# pi3_hat.net
KiCad netlist of a schematic drawn in EAGLE
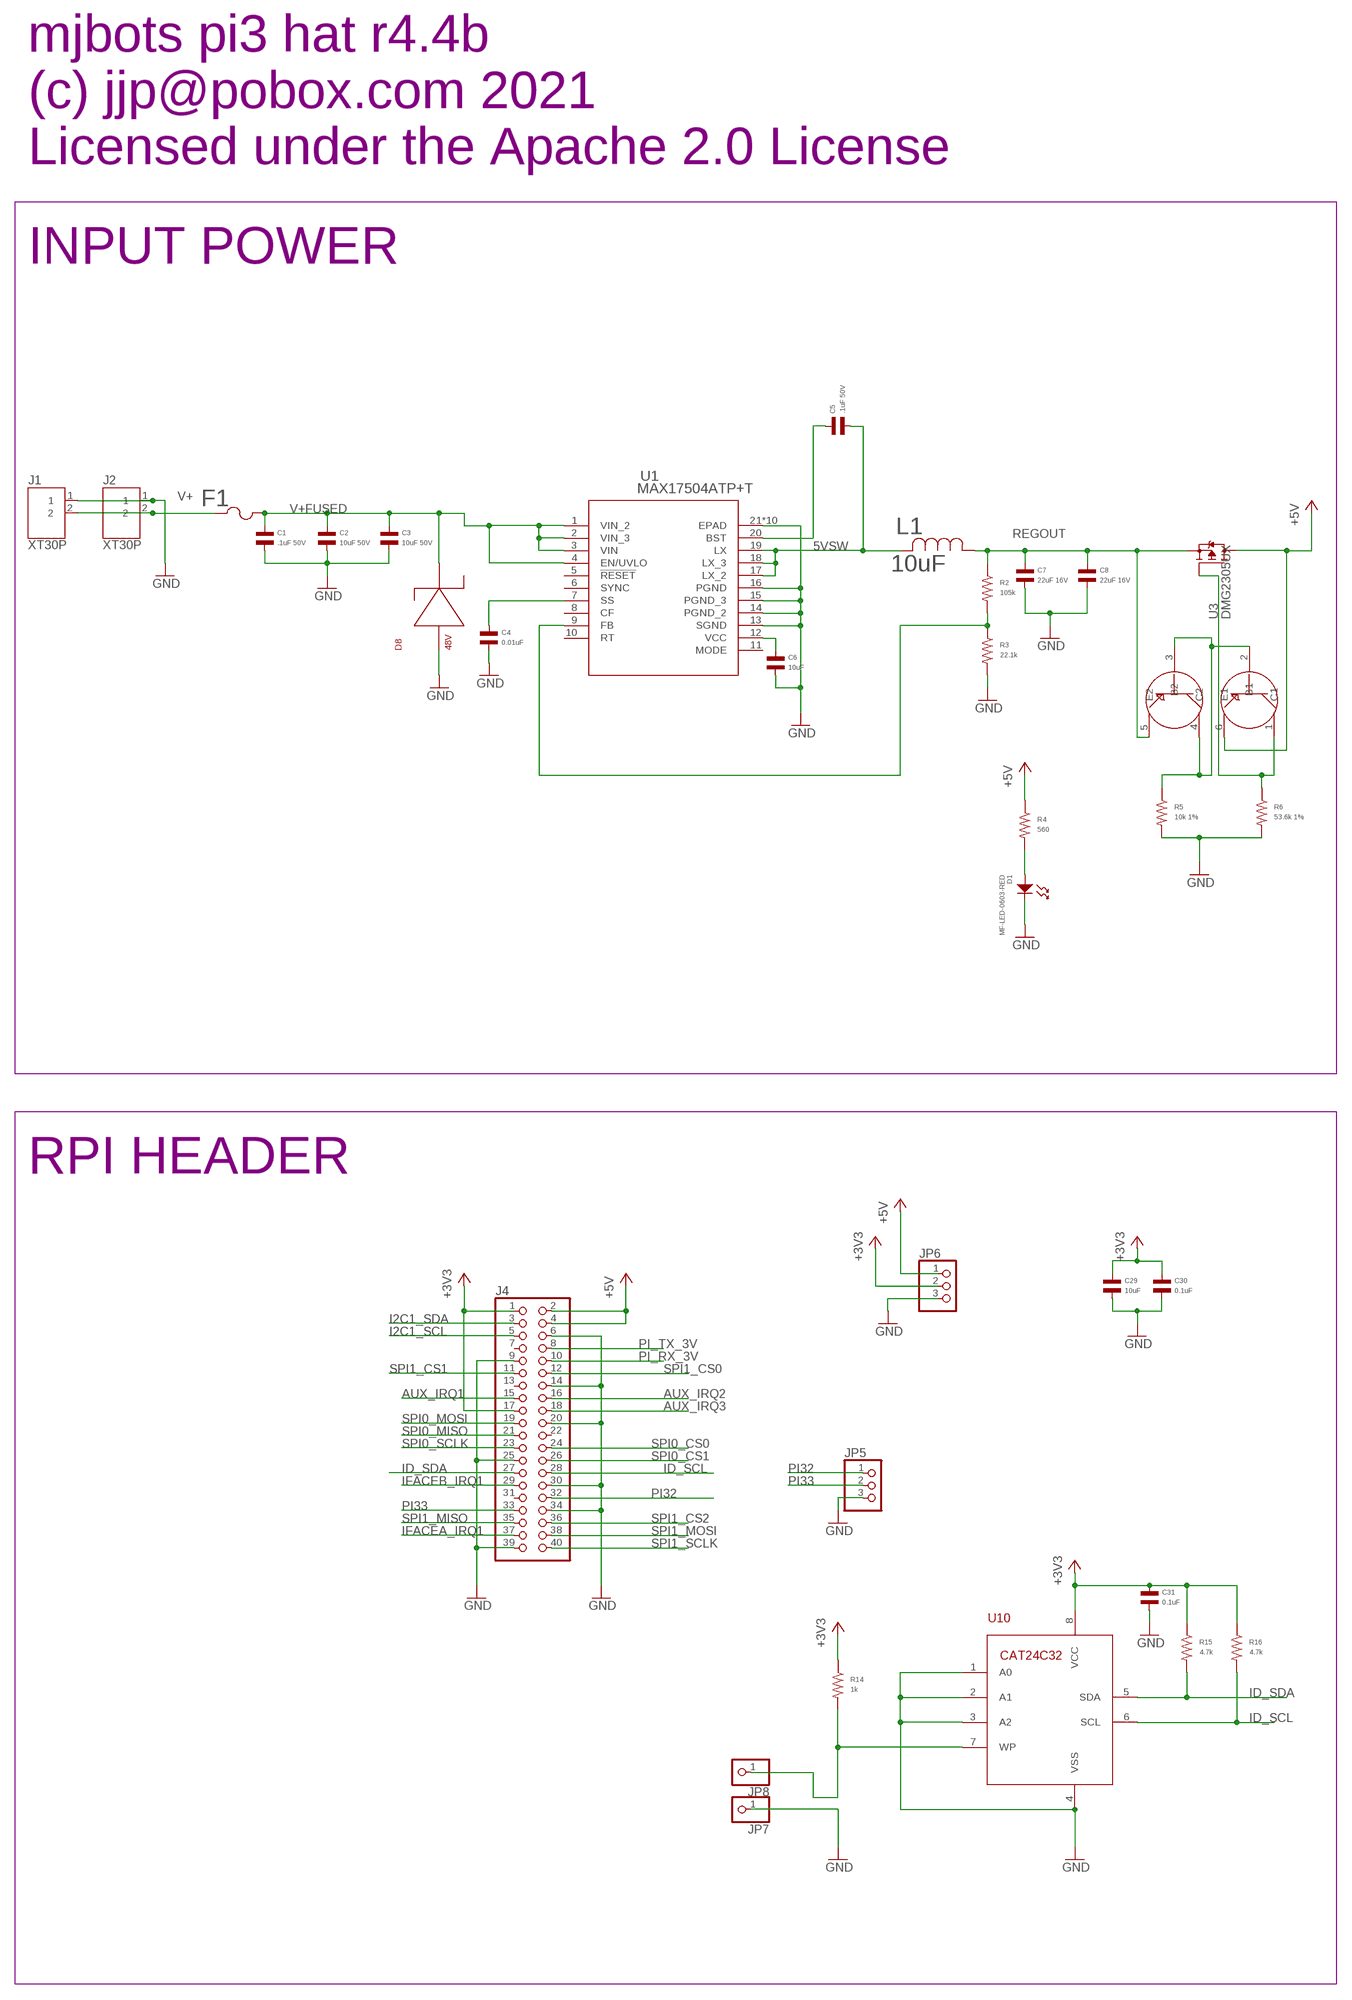
[diagram p0: schematic, sheet 1, part 1 of 3]
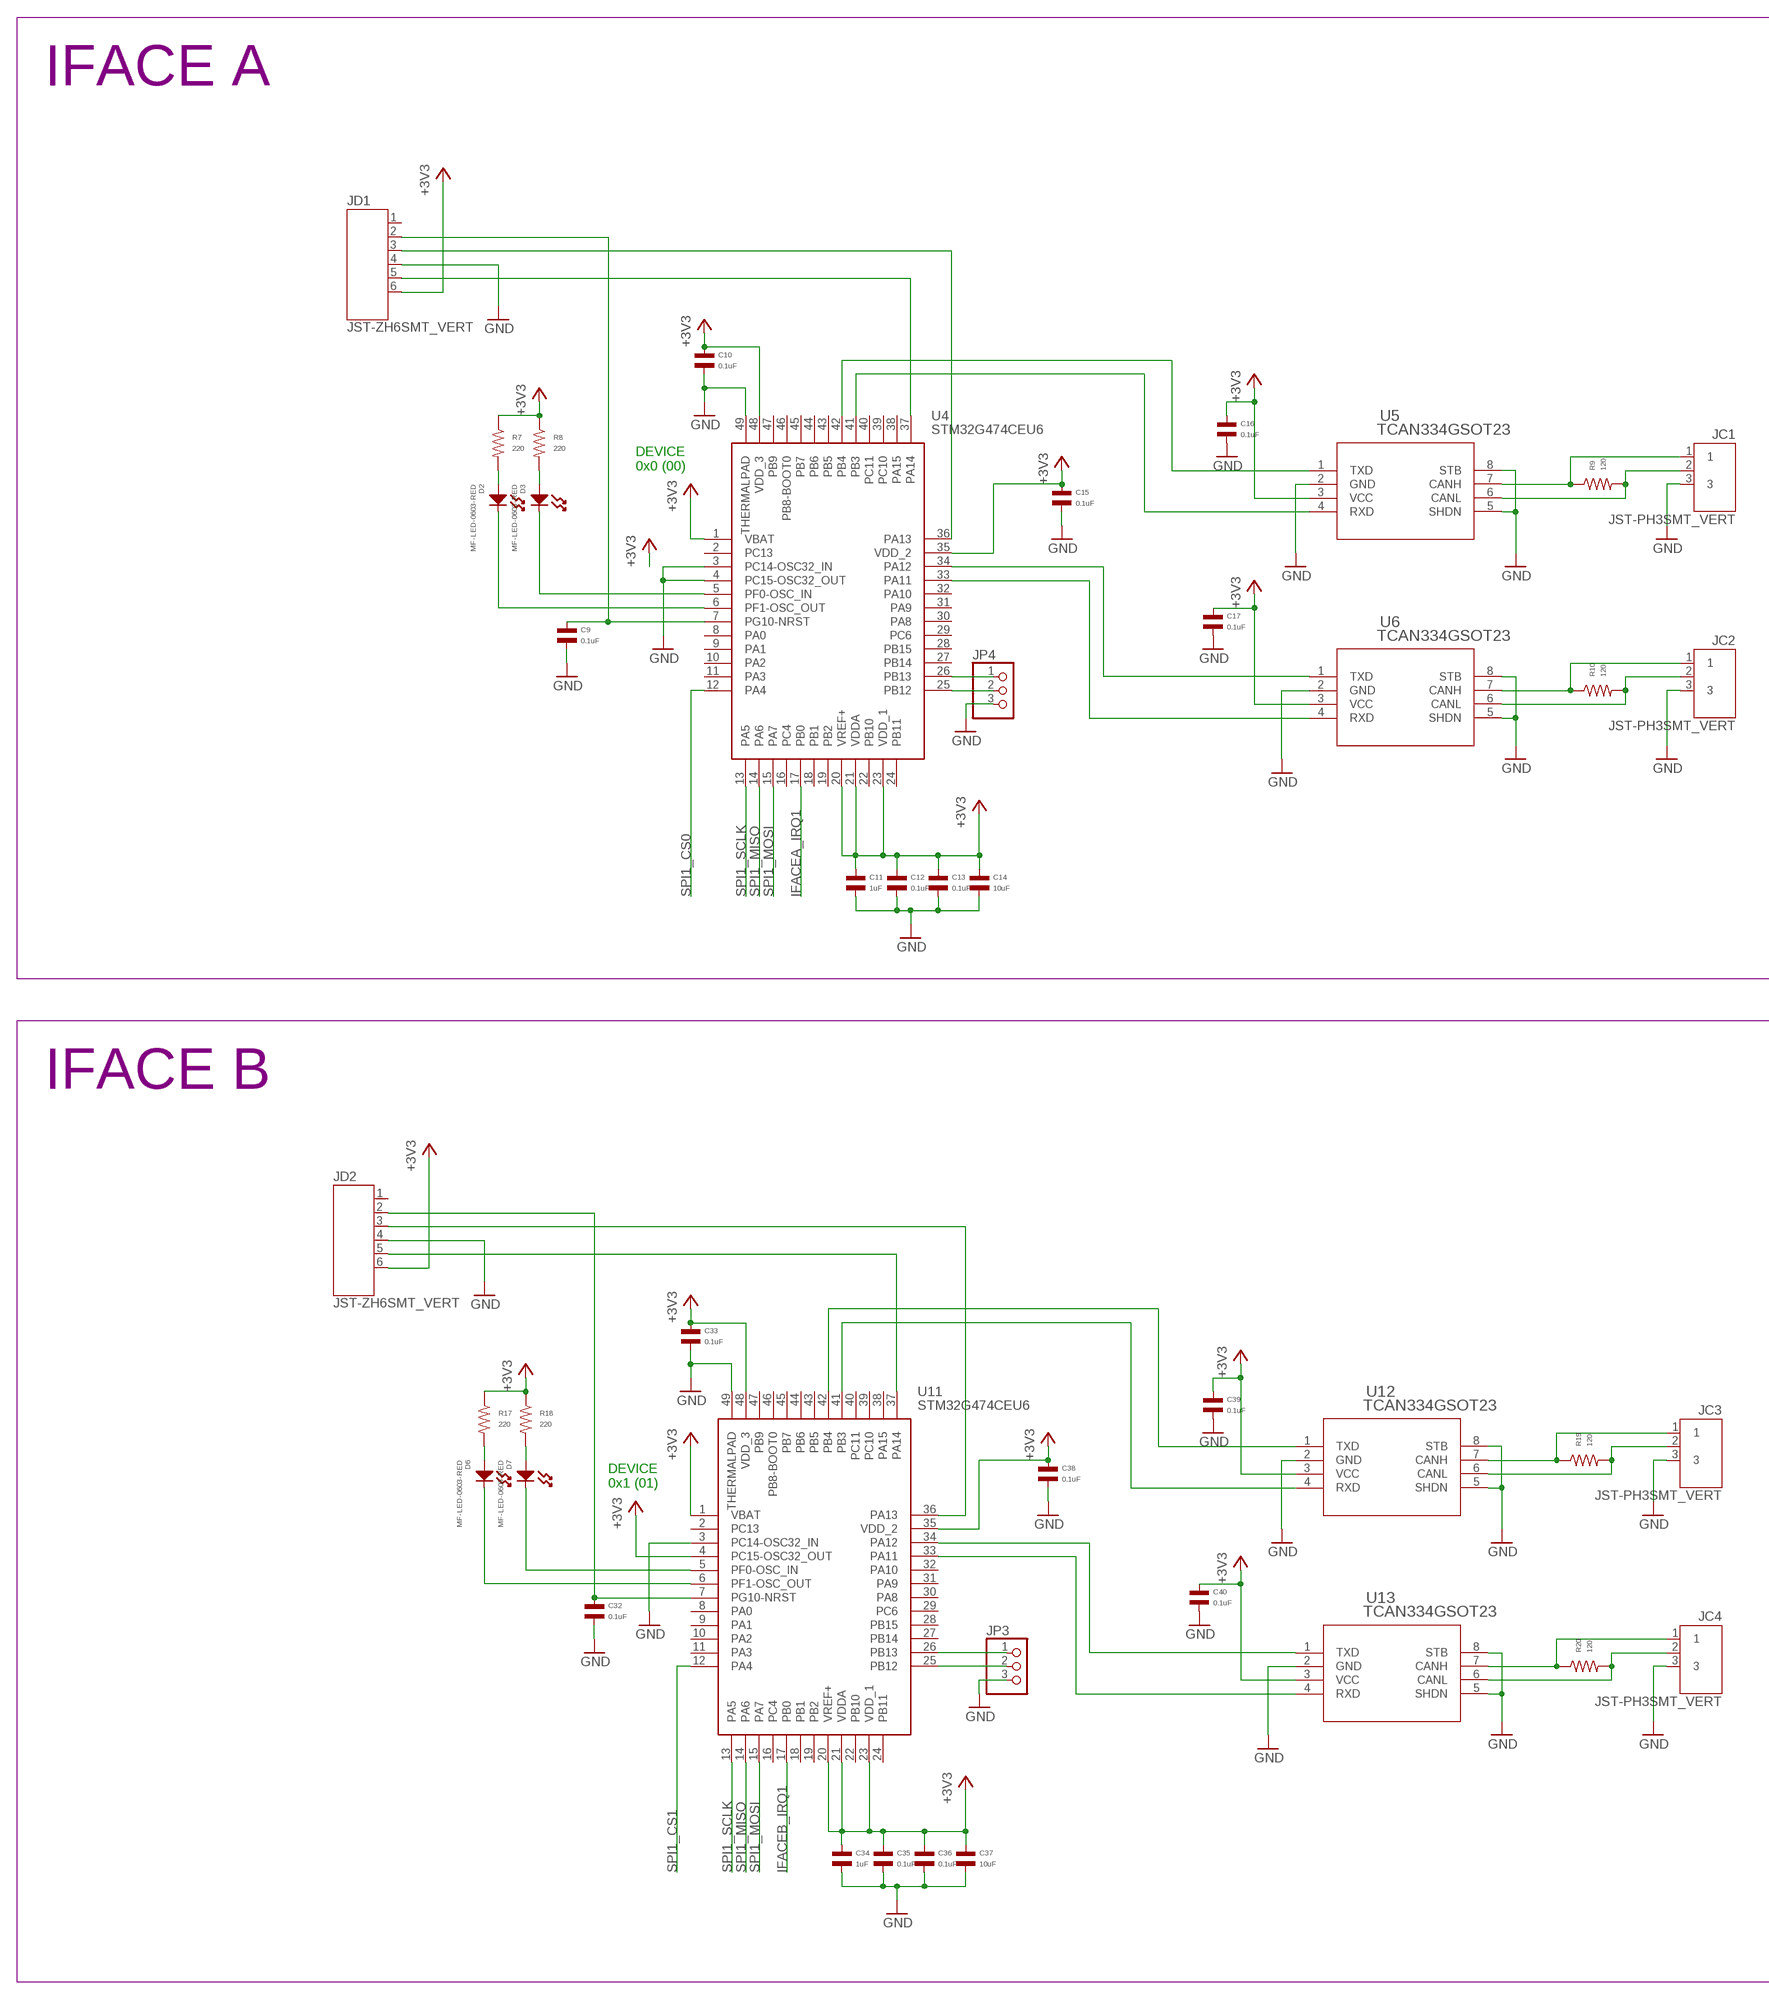
[diagram p1: schematic, sheet 1, part 2 of 3]
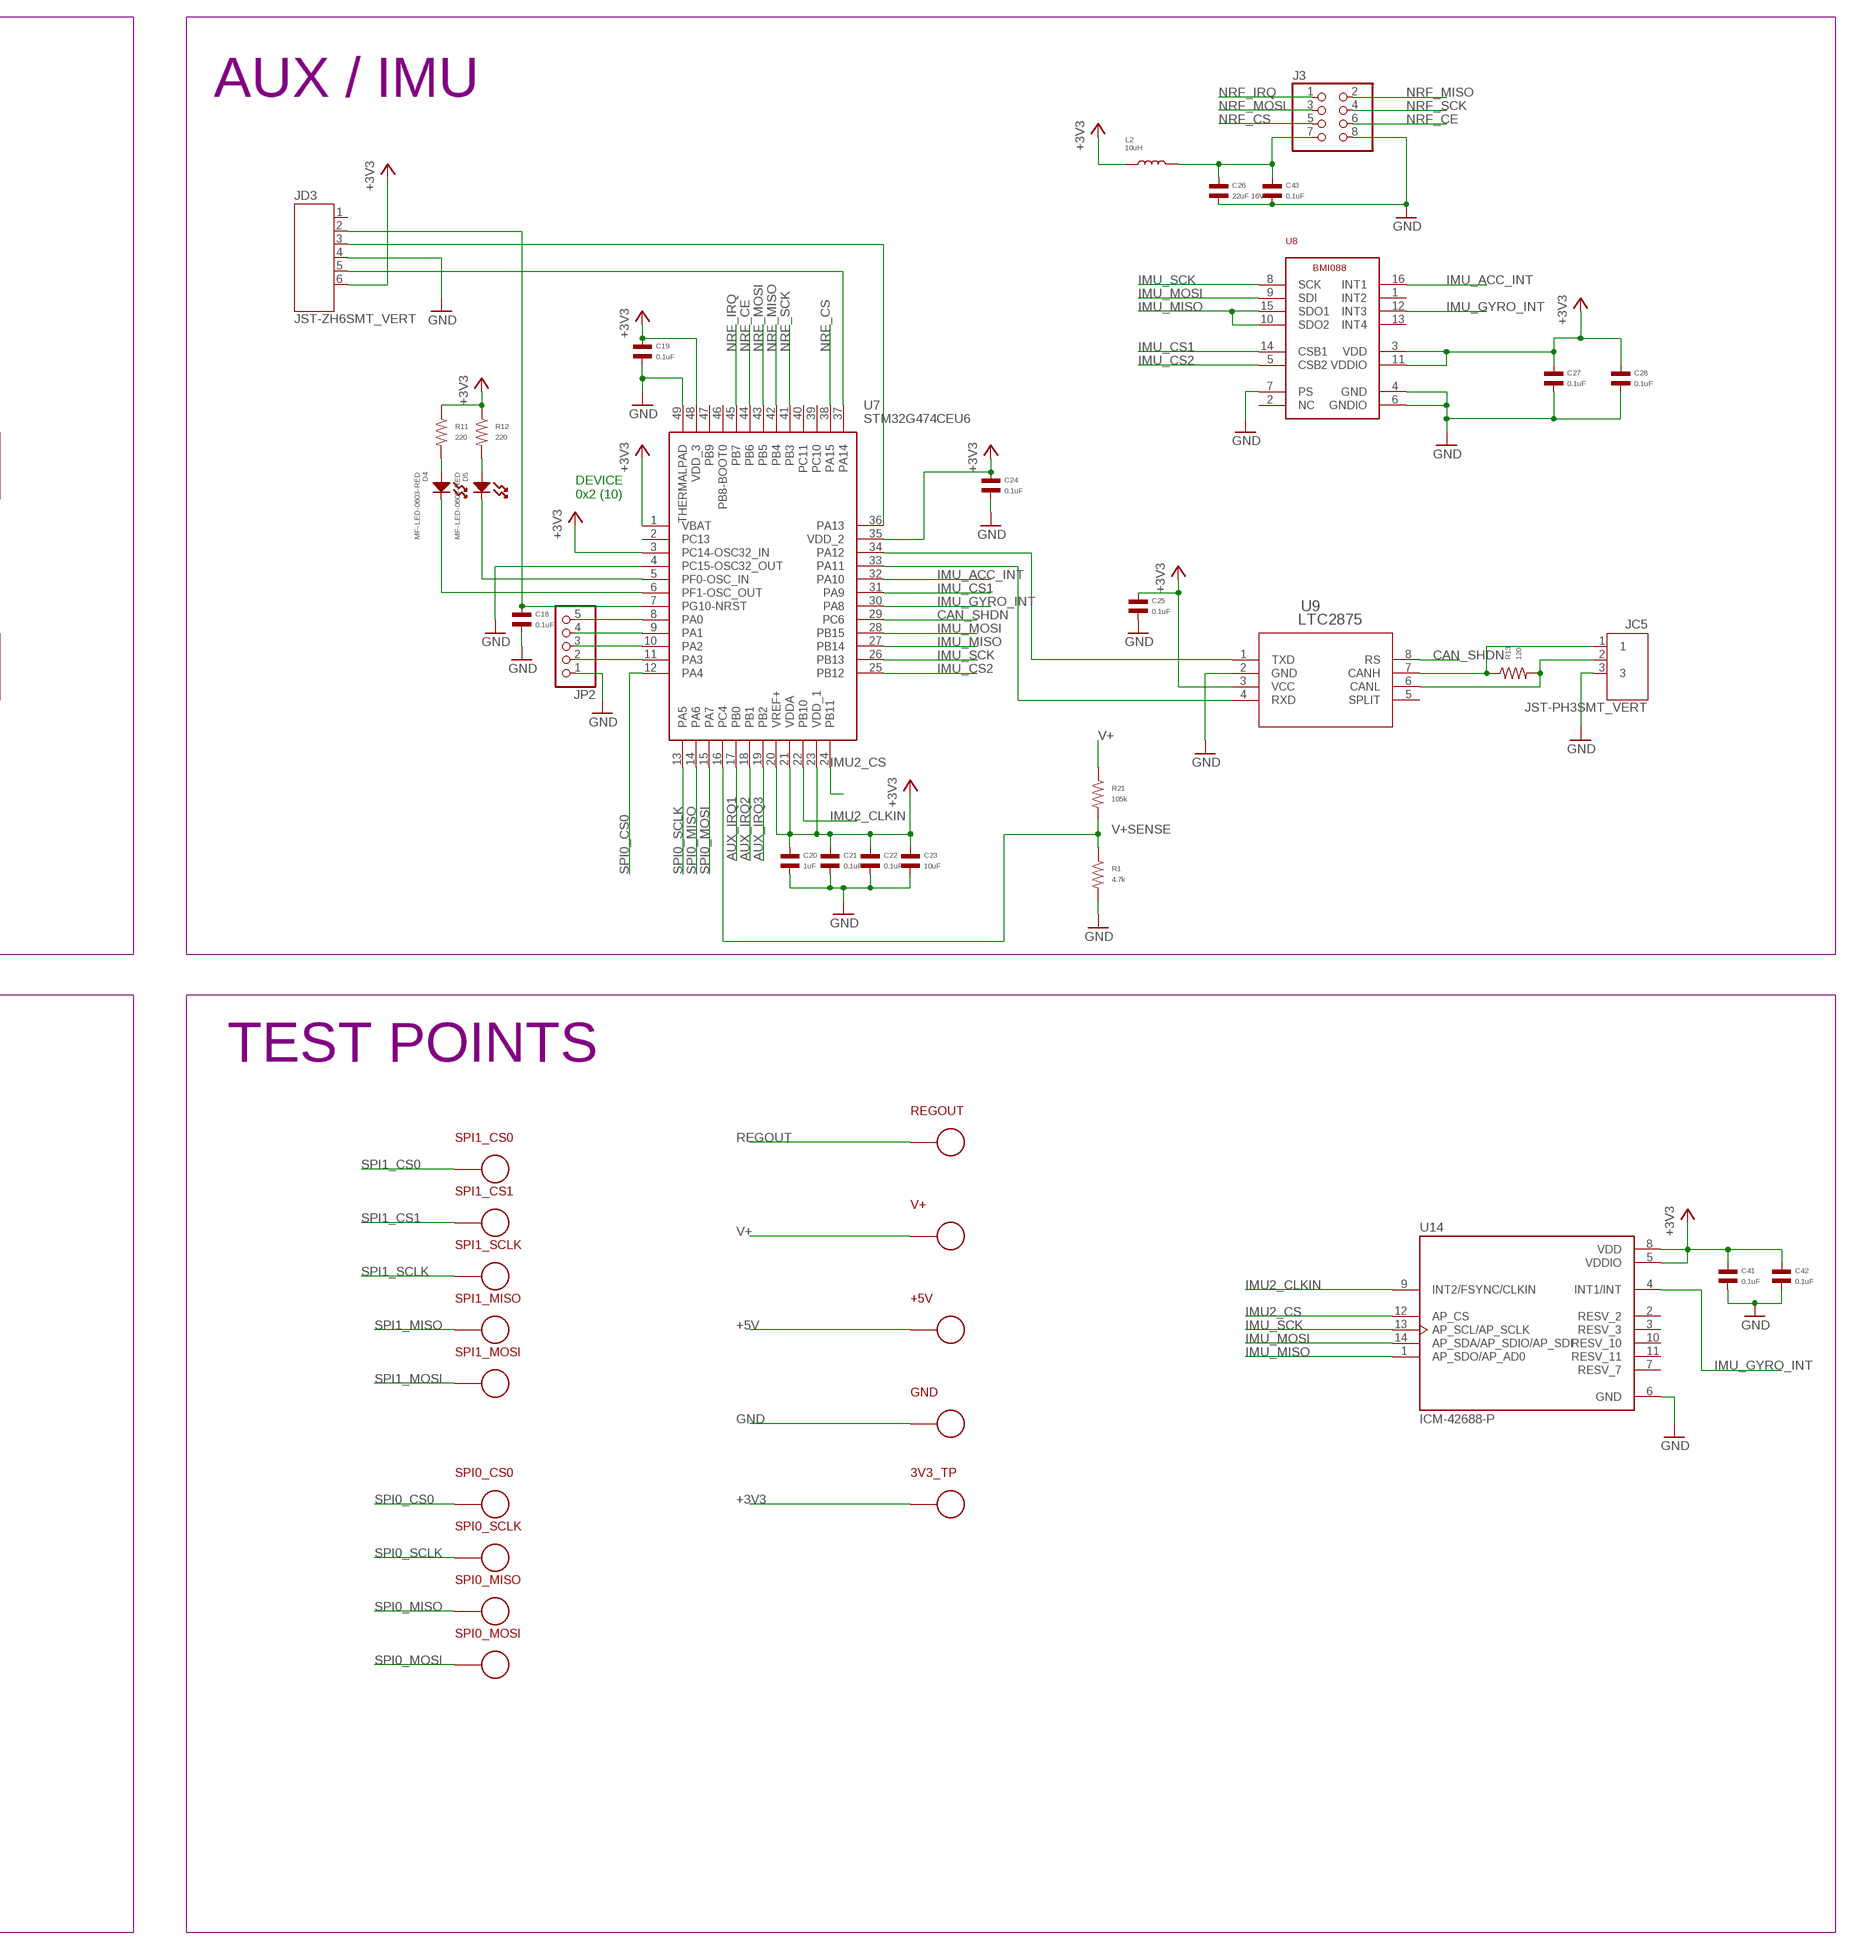
[diagram p2: schematic, sheet 1, part 3 of 3]

(export (version "E")
  (design (tool "Eeschema 10.0.6"))
  (components
    (comp (ref "+5V")
      (value "PAD24AWG_PAD")
      (footprint "eagle-import:24AWG_PAD")
      (libsource (lib "eagle-import") (part "PAD24AWG_PAD"))
    )
    (comp (ref "3V3_TP")
      (value "PAD24AWG_PAD")
      (footprint "eagle-import:24AWG_PAD")
      (libsource (lib "eagle-import") (part "PAD24AWG_PAD"))
    )
    (comp (ref "C1")
      (value ".1uF 50V")
      (footprint "eagle-import:C0805")
      (fields (field (name "HOUSEPART") "1") (field (name "MPN") "MF-CAP-0805-0.1uF"))
      (libsource (lib "eagle-import") (part "CAPACITOR_NP_0805"))
    )
    (comp (ref "C2")
      (value "10uF 50V")
      (footprint "eagle-import:C1206")
      (fields (field (name "MF") "TDK") (field (name "MPN") "C3216X7R1H106K160AE"))
      (libsource (lib "eagle-import") (part "CAPACITOR_NP_1206"))
    )
    (comp (ref "C3")
      (value "10uF 50V")
      (footprint "eagle-import:C1206")
      (fields (field (name "MF") "TDK") (field (name "MPN") "C3216X7R1H106K160AE"))
      (libsource (lib "eagle-import") (part "CAPACITOR_NP_1206"))
    )
    (comp (ref "C4")
      (value "0.01uF")
      (footprint "eagle-import:C0603")
      (fields (field (name "MPN") "MF-CAP-0603-0.01uF"))
      (libsource (lib "eagle-import") (part "CAPACITOR_NP_0603"))
    )
    (comp (ref "C5")
      (value ".1uF 50V")
      (footprint "eagle-import:C0805")
      (fields (field (name "HOUSEPART") "1") (field (name "MPN") "MF-CAP-0805-0.1uF"))
      (libsource (lib "eagle-import") (part "CAPACITOR_NP_0805"))
    )
    (comp (ref "C6")
      (value "10uF")
      (footprint "eagle-import:C1206")
      (fields (field (name "HOUSEPART") "YES") (field (name "MPN") "MF-CAP-1206-10uF"))
      (libsource (lib "eagle-import") (part "CAPACITOR_NP_1206"))
    )
    (comp (ref "C7")
      (value "22uF 16V")
      (footprint "eagle-import:C1210")
      (fields (field (name "MF") "SAMSUNG") (field (name "MPN") "CL32A226KOJNNNE"))
      (libsource (lib "eagle-import") (part "CAPACITOR_NP_1210"))
    )
    (comp (ref "C8")
      (value "22uF 16V")
      (footprint "eagle-import:C1210")
      (fields (field (name "MF") "SAMSUNG") (field (name "MPN") "CL32A226KOJNNNE"))
      (libsource (lib "eagle-import") (part "CAPACITOR_NP_1210"))
    )
    (comp (ref "C9")
      (value "0.1uF")
      (footprint "eagle-import:C0402")
      (fields (field (name "HOUSEPART") "YES") (field (name "MPN") "MF-CAP-0402-0.1uF"))
      (libsource (lib "eagle-import") (part "CAPACITOR_NP_0402"))
    )
    (comp (ref "C10")
      (value "0.1uF")
      (footprint "eagle-import:C0402")
      (fields (field (name "HOUSEPART") "YES") (field (name "MPN") "MF-CAP-0402-0.1uF"))
      (libsource (lib "eagle-import") (part "CAPACITOR_NP_0402"))
    )
    (comp (ref "C11")
      (value "1uF")
      (footprint "eagle-import:C0402")
      (fields (field (name "HOUSEPART") "YES") (field (name "MPN") "MF-CAP-0402-1uF"))
      (libsource (lib "eagle-import") (part "CAPACITOR_NP_0402"))
    )
    (comp (ref "C12")
      (value "0.1uF")
      (footprint "eagle-import:C0402")
      (fields (field (name "HOUSEPART") "YES") (field (name "MPN") "MF-CAP-0402-0.1uF"))
      (libsource (lib "eagle-import") (part "CAPACITOR_NP_0402"))
    )
    (comp (ref "C13")
      (value "0.1uF")
      (footprint "eagle-import:C0402")
      (fields (field (name "HOUSEPART") "YES") (field (name "MPN") "MF-CAP-0402-0.1uF"))
      (libsource (lib "eagle-import") (part "CAPACITOR_NP_0402"))
    )
    (comp (ref "C14")
      (value "10uF")
      (footprint "eagle-import:C1206")
      (fields (field (name "HOUSEPART") "YES") (field (name "MPN") "MF-CAP-1206-10uF"))
      (libsource (lib "eagle-import") (part "CAPACITOR_NP_1206"))
    )
    (comp (ref "C15")
      (value "0.1uF")
      (footprint "eagle-import:C0402")
      (fields (field (name "HOUSEPART") "YES") (field (name "MPN") "MF-CAP-0402-0.1uF"))
      (libsource (lib "eagle-import") (part "CAPACITOR_NP_0402"))
    )
    (comp (ref "C16")
      (value "0.1uF")
      (footprint "eagle-import:C0402")
      (fields (field (name "HOUSEPART") "YES") (field (name "MPN") "MF-CAP-0402-0.1uF"))
      (libsource (lib "eagle-import") (part "CAPACITOR_NP_0402"))
    )
    (comp (ref "C17")
      (value "0.1uF")
      (footprint "eagle-import:C0402")
      (fields (field (name "HOUSEPART") "YES") (field (name "MPN") "MF-CAP-0402-0.1uF"))
      (libsource (lib "eagle-import") (part "CAPACITOR_NP_0402"))
    )
    (comp (ref "C18")
      (value "0.1uF")
      (footprint "eagle-import:C0402")
      (fields (field (name "HOUSEPART") "YES") (field (name "MPN") "MF-CAP-0402-0.1uF"))
      (libsource (lib "eagle-import") (part "CAPACITOR_NP_0402"))
    )
    (comp (ref "C19")
      (value "0.1uF")
      (footprint "eagle-import:C0402")
      (fields (field (name "HOUSEPART") "YES") (field (name "MPN") "MF-CAP-0402-0.1uF"))
      (libsource (lib "eagle-import") (part "CAPACITOR_NP_0402"))
    )
    (comp (ref "C20")
      (value "1uF")
      (footprint "eagle-import:C0402")
      (fields (field (name "HOUSEPART") "YES") (field (name "MPN") "MF-CAP-0402-1uF"))
      (libsource (lib "eagle-import") (part "CAPACITOR_NP_0402"))
    )
    (comp (ref "C21")
      (value "0.1uF")
      (footprint "eagle-import:C0402")
      (fields (field (name "HOUSEPART") "YES") (field (name "MPN") "MF-CAP-0402-0.1uF"))
      (libsource (lib "eagle-import") (part "CAPACITOR_NP_0402"))
    )
    (comp (ref "C22")
      (value "0.1uF")
      (footprint "eagle-import:C0402")
      (fields (field (name "HOUSEPART") "YES") (field (name "MPN") "MF-CAP-0402-0.1uF"))
      (libsource (lib "eagle-import") (part "CAPACITOR_NP_0402"))
    )
    (comp (ref "C23")
      (value "10uF")
      (footprint "eagle-import:C1206")
      (fields (field (name "HOUSEPART") "YES") (field (name "MPN") "MF-CAP-1206-10uF"))
      (libsource (lib "eagle-import") (part "CAPACITOR_NP_1206"))
    )
    (comp (ref "C24")
      (value "0.1uF")
      (footprint "eagle-import:C0402")
      (fields (field (name "HOUSEPART") "YES") (field (name "MPN") "MF-CAP-0402-0.1uF"))
      (libsource (lib "eagle-import") (part "CAPACITOR_NP_0402"))
    )
    (comp (ref "C25")
      (value "0.1uF")
      (footprint "eagle-import:C0402")
      (fields (field (name "HOUSEPART") "YES") (field (name "MPN") "MF-CAP-0402-0.1uF"))
      (libsource (lib "eagle-import") (part "CAPACITOR_NP_0402"))
    )
    (comp (ref "C26")
      (value "22uF 16V")
      (footprint "eagle-import:C1210")
      (fields (field (name "MF") "SAMSUNG") (field (name "MPN") "CL32A226KOJNNNE"))
      (libsource (lib "eagle-import") (part "CAPACITOR_NP_1210"))
    )
    (comp (ref "C27")
      (value "0.1uF")
      (footprint "eagle-import:C0402")
      (fields (field (name "HOUSEPART") "YES") (field (name "MPN") "MF-CAP-0402-0.1uF"))
      (libsource (lib "eagle-import") (part "CAPACITOR_NP_0402"))
    )
    (comp (ref "C28")
      (value "0.1uF")
      (footprint "eagle-import:C0402")
      (fields (field (name "HOUSEPART") "YES") (field (name "MPN") "MF-CAP-0402-0.1uF"))
      (libsource (lib "eagle-import") (part "CAPACITOR_NP_0402"))
    )
    (comp (ref "C29")
      (value "10uF")
      (footprint "eagle-import:C1206")
      (fields (field (name "HOUSEPART") "YES") (field (name "MPN") "MF-CAP-1206-10uF"))
      (libsource (lib "eagle-import") (part "CAPACITOR_NP_1206"))
    )
    (comp (ref "C30")
      (value "0.1uF")
      (footprint "eagle-import:C0402")
      (fields (field (name "HOUSEPART") "YES") (field (name "MPN") "MF-CAP-0402-0.1uF"))
      (libsource (lib "eagle-import") (part "CAPACITOR_NP_0402"))
    )
    (comp (ref "C31")
      (value "0.1uF")
      (footprint "eagle-import:C0402")
      (fields (field (name "HOUSEPART") "YES") (field (name "MPN") "MF-CAP-0402-0.1uF"))
      (libsource (lib "eagle-import") (part "CAPACITOR_NP_0402"))
    )
    (comp (ref "C32")
      (value "0.1uF")
      (footprint "eagle-import:C0402")
      (fields (field (name "HOUSEPART") "YES") (field (name "MPN") "MF-CAP-0402-0.1uF"))
      (libsource (lib "eagle-import") (part "CAPACITOR_NP_0402"))
    )
    (comp (ref "C33")
      (value "0.1uF")
      (footprint "eagle-import:C0402")
      (fields (field (name "HOUSEPART") "YES") (field (name "MPN") "MF-CAP-0402-0.1uF"))
      (libsource (lib "eagle-import") (part "CAPACITOR_NP_0402"))
    )
    (comp (ref "C34")
      (value "1uF")
      (footprint "eagle-import:C0402")
      (fields (field (name "HOUSEPART") "YES") (field (name "MPN") "MF-CAP-0402-1uF"))
      (libsource (lib "eagle-import") (part "CAPACITOR_NP_0402"))
    )
    (comp (ref "C35")
      (value "0.1uF")
      (footprint "eagle-import:C0402")
      (fields (field (name "HOUSEPART") "YES") (field (name "MPN") "MF-CAP-0402-0.1uF"))
      (libsource (lib "eagle-import") (part "CAPACITOR_NP_0402"))
    )
    (comp (ref "C36")
      (value "0.1uF")
      (footprint "eagle-import:C0402")
      (fields (field (name "HOUSEPART") "YES") (field (name "MPN") "MF-CAP-0402-0.1uF"))
      (libsource (lib "eagle-import") (part "CAPACITOR_NP_0402"))
    )
    (comp (ref "C37")
      (value "10uF")
      (footprint "eagle-import:C1206")
      (fields (field (name "HOUSEPART") "YES") (field (name "MPN") "MF-CAP-1206-10uF"))
      (libsource (lib "eagle-import") (part "CAPACITOR_NP_1206"))
    )
    (comp (ref "C38")
      (value "0.1uF")
      (footprint "eagle-import:C0402")
      (fields (field (name "HOUSEPART") "YES") (field (name "MPN") "MF-CAP-0402-0.1uF"))
      (libsource (lib "eagle-import") (part "CAPACITOR_NP_0402"))
    )
    (comp (ref "C39")
      (value "0.1uF")
      (footprint "eagle-import:C0402")
      (fields (field (name "HOUSEPART") "YES") (field (name "MPN") "MF-CAP-0402-0.1uF"))
      (libsource (lib "eagle-import") (part "CAPACITOR_NP_0402"))
    )
    (comp (ref "C40")
      (value "0.1uF")
      (footprint "eagle-import:C0402")
      (fields (field (name "HOUSEPART") "YES") (field (name "MPN") "MF-CAP-0402-0.1uF"))
      (libsource (lib "eagle-import") (part "CAPACITOR_NP_0402"))
    )
    (comp (ref "C41")
      (value "0.1uF")
      (footprint "eagle-import:C0402")
      (fields (field (name "HOUSEPART") "YES") (field (name "MPN") "MF-CAP-0402-0.1uF"))
      (libsource (lib "eagle-import") (part "CAPACITOR_NP_0402"))
    )
    (comp (ref "C42")
      (value "0.1uF")
      (footprint "eagle-import:C0402")
      (fields (field (name "HOUSEPART") "YES") (field (name "MPN") "MF-CAP-0402-0.1uF"))
      (libsource (lib "eagle-import") (part "CAPACITOR_NP_0402"))
    )
    (comp (ref "C43")
      (value "0.1uF")
      (footprint "eagle-import:C0402")
      (fields (field (name "HOUSEPART") "YES") (field (name "MPN") "MF-CAP-0402-0.1uF"))
      (libsource (lib "eagle-import") (part "CAPACITOR_NP_0402"))
    )
    (comp (ref "D1")
      (value "MF-LED-0603-RED")
      (footprint "eagle-import:LED0603")
      (fields (field (name "HOUSEPART") "YES"))
      (libsource (lib "eagle-import") (part "LED_SINGLE-0603-RED"))
    )
    (comp (ref "D2")
      (value "MF-LED-0603-RED")
      (footprint "eagle-import:LED0603")
      (fields (field (name "HOUSEPART") "YES"))
      (libsource (lib "eagle-import") (part "LED_SINGLE-0603-RED"))
    )
    (comp (ref "D3")
      (value "MF-LED-0603-RED")
      (footprint "eagle-import:LED0603")
      (fields (field (name "HOUSEPART") "YES") (field (name "MPN") "MF-LED-0603-GREEN"))
      (libsource (lib "eagle-import") (part "LED_SINGLE-0603-RED"))
    )
    (comp (ref "D4")
      (value "MF-LED-0603-RED")
      (footprint "eagle-import:LED0603")
      (fields (field (name "HOUSEPART") "YES"))
      (libsource (lib "eagle-import") (part "LED_SINGLE-0603-RED"))
    )
    (comp (ref "D5")
      (value "MF-LED-0603-RED")
      (footprint "eagle-import:LED0603")
      (fields (field (name "HOUSEPART") "YES") (field (name "MPN") "MF-LED-0603-GREEN"))
      (libsource (lib "eagle-import") (part "LED_SINGLE-0603-RED"))
    )
    (comp (ref "D6")
      (value "MF-LED-0603-RED")
      (footprint "eagle-import:LED0603")
      (fields (field (name "HOUSEPART") "YES"))
      (libsource (lib "eagle-import") (part "LED_SINGLE-0603-RED"))
    )
    (comp (ref "D7")
      (value "MF-LED-0603-RED")
      (footprint "eagle-import:LED0603")
      (fields (field (name "HOUSEPART") "YES") (field (name "MPN") "MF-LED-0603-GREEN"))
      (libsource (lib "eagle-import") (part "LED_SINGLE-0603-RED"))
    )
    (comp (ref "D8")
      (value "48V")
      (footprint "eagle-import:SMF")
      (fields (field (name "MF") "Vishay") (field (name "MPN") "SMF48A-E3-08"))
      (libsource (lib "eagle-import") (part "SMF"))
    )
    (comp (ref "F1")
      (value "MFU0603FF04000P100")
      (footprint "eagle-import:FUS_VISHAY_MFU0603")
      (fields
        (field (name "MF") "BEL FUSE")
        (field (name "MPN") "0686F4000-01")
        (field (name "VENDOR") "BEL FUSE")
      )
      (libsource (lib "eagle-import") (part "MFU0603FF04000P100"))
    )
    (comp (ref "GND")
      (value "PAD24AWG_PAD")
      (footprint "eagle-import:24AWG_PAD")
      (libsource (lib "eagle-import") (part "PAD24AWG_PAD"))
    )
    (comp (ref "J1")
      (value "XT30P")
      (footprint "eagle-import:XT30P")
      (libsource (lib "eagle-import") (part "XT30P"))
    )
    (comp (ref "J2")
      (value "XT30P")
      (footprint "eagle-import:XT30P")
      (libsource (lib "eagle-import") (part "XT30P"))
    )
    (comp (ref "J3")
      (value "PINHD-2X4")
      (footprint "eagle-import:2X04")
      (libsource (lib "eagle-import") (part "PINHD-2X4"))
    )
    (comp (ref "J4")
      (value "PI3_HEADER2X20-FLIP")
      (footprint "eagle-import:2X20FLIP")
      (fields (field (name "MF") "SULLINS") (field (name "MPN") "PPPC202LFBN-RC"))
      (libsource (lib "eagle-import") (part "PI3_HEADER2X20-FLIP"))
    )
    (comp (ref "JC1")
      (value "JST-PH3SMT_VERT")
      (footprint "eagle-import:JST_B3B_PH-SM4-TB(LF)(SN)")
      (fields (field (name "MF") "JST") (field (name "MPN") "B3B-PH-SM4-TB(LF)(SN)"))
      (libsource (lib "eagle-import") (part "JST-PH3SMT_VERT"))
    )
    (comp (ref "JC2")
      (value "JST-PH3SMT_VERT")
      (footprint "eagle-import:JST_B3B_PH-SM4-TB(LF)(SN)")
      (fields (field (name "MF") "JST") (field (name "MPN") "B3B-PH-SM4-TB(LF)(SN)"))
      (libsource (lib "eagle-import") (part "JST-PH3SMT_VERT"))
    )
    (comp (ref "JC3")
      (value "JST-PH3SMT_VERT")
      (footprint "eagle-import:JST_B3B_PH-SM4-TB(LF)(SN)")
      (fields (field (name "MF") "JST") (field (name "MPN") "B3B-PH-SM4-TB(LF)(SN)"))
      (libsource (lib "eagle-import") (part "JST-PH3SMT_VERT"))
    )
    (comp (ref "JC4")
      (value "JST-PH3SMT_VERT")
      (footprint "eagle-import:JST_B3B_PH-SM4-TB(LF)(SN)")
      (fields (field (name "MF") "JST") (field (name "MPN") "B3B-PH-SM4-TB(LF)(SN)"))
      (libsource (lib "eagle-import") (part "JST-PH3SMT_VERT"))
    )
    (comp (ref "JC5")
      (value "JST-PH3SMT_VERT")
      (footprint "eagle-import:JST_B3B_PH-SM4-TB(LF)(SN)")
      (fields (field (name "MF") "JST") (field (name "MPN") "B3B-PH-SM4-TB(LF)(SN)"))
      (libsource (lib "eagle-import") (part "JST-PH3SMT_VERT"))
    )
    (comp (ref "JD1")
      (value "JST-ZH6SMT_VERT")
      (footprint "eagle-import:JST_B6B-ZR-SM4-TF(LF)(SN)")
      (fields (field (name "MF") "JST") (field (name "MPN") "B6B-ZR-SM4-TF(LF)(SN)"))
      (libsource (lib "eagle-import") (part "JST-ZH6SMT_VERT"))
    )
    (comp (ref "JD2")
      (value "JST-ZH6SMT_VERT")
      (footprint "eagle-import:JST_B6B-ZR-SM4-TF(LF)(SN)")
      (fields (field (name "MF") "JST") (field (name "MPN") "B6B-ZR-SM4-TF(LF)(SN)"))
      (libsource (lib "eagle-import") (part "JST-ZH6SMT_VERT"))
    )
    (comp (ref "JD3")
      (value "JST-ZH6SMT_VERT")
      (footprint "eagle-import:JST_B6B-ZR-SM4-TF(LF)(SN)")
      (fields (field (name "MF") "JST") (field (name "MPN") "B6B-ZR-SM4-TF(LF)(SN)"))
      (libsource (lib "eagle-import") (part "JST-ZH6SMT_VERT"))
    )
    (comp (ref "JP2")
      (value "PINHD-1X5")
      (footprint "eagle-import:1X05")
      (fields (field (name "MF") "MacroFab") (field (name "MPN") "MF-CON-2.54mm-01x05"))
      (libsource (lib "eagle-import") (part "PINHD-1X5"))
    )
    (comp (ref "JP3")
      (value "PINHD-1X3")
      (footprint "eagle-import:1X03")
      (fields (field (name "MF") "MacroFab") (field (name "MPN") "MF-CON-2.54mm-01x03"))
      (libsource (lib "eagle-import") (part "PINHD-1X3"))
    )
    (comp (ref "JP4")
      (value "PINHD-1X3")
      (footprint "eagle-import:1X03")
      (fields (field (name "MF") "MacroFab") (field (name "MPN") "MF-CON-2.54mm-01x03"))
      (libsource (lib "eagle-import") (part "PINHD-1X3"))
    )
    (comp (ref "JP5")
      (value "PINHD-1X3")
      (footprint "eagle-import:1X03")
      (fields (field (name "MF") "MacroFab") (field (name "MPN") "MF-CON-2.54mm-01x03"))
      (libsource (lib "eagle-import") (part "PINHD-1X3"))
    )
    (comp (ref "JP6")
      (value "PINHD-1X3")
      (footprint "eagle-import:1X03")
      (fields (field (name "MF") "MacroFab") (field (name "MPN") "MF-CON-2.54mm-01x03"))
      (libsource (lib "eagle-import") (part "PINHD-1X3"))
    )
    (comp (ref "JP7")
      (value "PINHD-1X1")
      (footprint "eagle-import:1X01")
      (libsource (lib "eagle-import") (part "PINHD-1X1"))
    )
    (comp (ref "JP8")
      (value "PINHD-1X1")
      (footprint "eagle-import:1X01")
      (libsource (lib "eagle-import") (part "PINHD-1X1"))
    )
    (comp (ref "L1")
      (value "10uF")
      (footprint "eagle-import:IND_YUDEN_NS10165_YDN")
      (fields (field (name "MANUFACTURER_PART_NUMBER") "NS10165T100MNA"))
      (libsource (lib "eagle-import") (part "NS10165T100MNA"))
    )
    (comp (ref "L2")
      (value "10uH")
      (footprint "eagle-import:L1210")
      (fields (field (name "MPN") "MF-IND-1210-10uH"))
      (libsource (lib "eagle-import") (part "INDUCTOR_1210"))
    )
    (comp (ref "R1")
      (value "4.7k")
      (footprint "eagle-import:R0402")
      (fields (field (name "HOUSEPART") "YES") (field (name "MPN") "MF-RES-0402-4.7K"))
      (libsource (lib "eagle-import") (part "RESISTOR_0402"))
    )
    (comp (ref "R2")
      (value "105k")
      (footprint "eagle-import:R0402")
      (fields (field (name "MF") "YAGEO") (field (name "MPN") "RC0402FR-07105KL"))
      (libsource (lib "eagle-import") (part "RESISTOR_0402"))
    )
    (comp (ref "R3")
      (value "22.1k")
      (footprint "eagle-import:R0402")
      (fields (field (name "MF") "YAGEO") (field (name "MPN") "RC0402FR-0722K1L"))
      (libsource (lib "eagle-import") (part "RESISTOR_0402"))
    )
    (comp (ref "R4")
      (value "560")
      (footprint "eagle-import:R0402")
      (fields (field (name "HOUSEPART") "YES") (field (name "MPN") "MF-RES-0402-560"))
      (libsource (lib "eagle-import") (part "RESISTOR_0402"))
    )
    (comp (ref "R5")
      (value "10k 1%")
      (footprint "eagle-import:R0603")
      (fields (field (name "MF") "YAGEO") (field (name "MPN") "RC0603FR-0710KL"))
      (libsource (lib "eagle-import") (part "RESISTOR_0603"))
    )
    (comp (ref "R6")
      (value "53.6k 1%")
      (footprint "eagle-import:R0603")
      (fields (field (name "MF") "YAGEO") (field (name "MPN") "RC0603FR-0753K6L"))
      (libsource (lib "eagle-import") (part "RESISTOR_0603"))
    )
    (comp (ref "R7")
      (value "220")
      (footprint "eagle-import:R0402")
      (fields (field (name "HOUSEPART") "YES") (field (name "MPN") "MF-RES-0402-220"))
      (libsource (lib "eagle-import") (part "RESISTOR_0402"))
    )
    (comp (ref "R8")
      (value "220")
      (footprint "eagle-import:R0402")
      (fields (field (name "HOUSEPART") "YES") (field (name "MPN") "MF-RES-0402-220"))
      (libsource (lib "eagle-import") (part "RESISTOR_0402"))
    )
    (comp (ref "R9")
      (value "120")
      (footprint "eagle-import:R0402")
      (fields (field (name "HOUSEPART") "YES") (field (name "MPN") "MF-RES-0402-100"))
      (libsource (lib "eagle-import") (part "RESISTOR_0402"))
    )
    (comp (ref "R10")
      (value "120")
      (footprint "eagle-import:R0402")
      (fields (field (name "HOUSEPART") "YES") (field (name "MPN") "MF-RES-0402-100"))
      (libsource (lib "eagle-import") (part "RESISTOR_0402"))
    )
    (comp (ref "R11")
      (value "220")
      (footprint "eagle-import:R0402")
      (fields (field (name "HOUSEPART") "YES") (field (name "MPN") "MF-RES-0402-220"))
      (libsource (lib "eagle-import") (part "RESISTOR_0402"))
    )
    (comp (ref "R12")
      (value "220")
      (footprint "eagle-import:R0402")
      (fields (field (name "HOUSEPART") "YES") (field (name "MPN") "MF-RES-0402-220"))
      (libsource (lib "eagle-import") (part "RESISTOR_0402"))
    )
    (comp (ref "R13")
      (value "120")
      (footprint "eagle-import:R0402")
      (fields (field (name "HOUSEPART") "YES") (field (name "MPN") "MF-RES-0402-100"))
      (libsource (lib "eagle-import") (part "RESISTOR_0402"))
    )
    (comp (ref "R14")
      (value "1k")
      (footprint "eagle-import:R0402")
      (fields (field (name "HOUSEPART") "YES") (field (name "MPN") "MF-RES-0402-1K"))
      (libsource (lib "eagle-import") (part "RESISTOR_0402"))
    )
    (comp (ref "R15")
      (value "4.7k")
      (footprint "eagle-import:R0402")
      (fields (field (name "HOUSEPART") "YES") (field (name "MPN") "MF-RES-0402-4.7K"))
      (libsource (lib "eagle-import") (part "RESISTOR_0402"))
    )
    (comp (ref "R16")
      (value "4.7k")
      (footprint "eagle-import:R0402")
      (fields (field (name "HOUSEPART") "YES") (field (name "MPN") "MF-RES-0402-4.7K"))
      (libsource (lib "eagle-import") (part "RESISTOR_0402"))
    )
    (comp (ref "R17")
      (value "220")
      (footprint "eagle-import:R0402")
      (fields (field (name "HOUSEPART") "YES") (field (name "MPN") "MF-RES-0402-220"))
      (libsource (lib "eagle-import") (part "RESISTOR_0402"))
    )
    (comp (ref "R18")
      (value "220")
      (footprint "eagle-import:R0402")
      (fields (field (name "HOUSEPART") "YES") (field (name "MPN") "MF-RES-0402-220"))
      (libsource (lib "eagle-import") (part "RESISTOR_0402"))
    )
    (comp (ref "R19")
      (value "120")
      (footprint "eagle-import:R0402")
      (fields (field (name "HOUSEPART") "YES") (field (name "MPN") "MF-RES-0402-100"))
      (libsource (lib "eagle-import") (part "RESISTOR_0402"))
    )
    (comp (ref "R20")
      (value "120")
      (footprint "eagle-import:R0402")
      (fields (field (name "HOUSEPART") "YES") (field (name "MPN") "MF-RES-0402-100"))
      (libsource (lib "eagle-import") (part "RESISTOR_0402"))
    )
    (comp (ref "R21")
      (value "105k")
      (footprint "eagle-import:R0402")
      (fields (field (name "MF") "YAGEO") (field (name "MPN") "RC0402FR-07105KL"))
      (libsource (lib "eagle-import") (part "RESISTOR_0402"))
    )
    (comp (ref "REGOUT")
      (value "PAD24AWG_PAD")
      (footprint "eagle-import:24AWG_PAD")
      (libsource (lib "eagle-import") (part "PAD24AWG_PAD"))
    )
    (comp (ref "SPI0_CS0")
      (value "PAD24AWG_PAD")
      (footprint "eagle-import:24AWG_PAD")
      (libsource (lib "eagle-import") (part "PAD24AWG_PAD"))
    )
    (comp (ref "SPI0_MISO")
      (value "PAD24AWG_PAD")
      (footprint "eagle-import:24AWG_PAD")
      (libsource (lib "eagle-import") (part "PAD24AWG_PAD"))
    )
    (comp (ref "SPI0_MOSI")
      (value "PAD24AWG_PAD")
      (footprint "eagle-import:24AWG_PAD")
      (libsource (lib "eagle-import") (part "PAD24AWG_PAD"))
    )
    (comp (ref "SPI0_SCLK")
      (value "PAD24AWG_PAD")
      (footprint "eagle-import:24AWG_PAD")
      (libsource (lib "eagle-import") (part "PAD24AWG_PAD"))
    )
    (comp (ref "SPI1_CS0")
      (value "PAD24AWG_PAD")
      (footprint "eagle-import:24AWG_PAD")
      (libsource (lib "eagle-import") (part "PAD24AWG_PAD"))
    )
    (comp (ref "SPI1_CS1")
      (value "PAD24AWG_PAD")
      (footprint "eagle-import:24AWG_PAD")
      (libsource (lib "eagle-import") (part "PAD24AWG_PAD"))
    )
    (comp (ref "SPI1_MISO")
      (value "PAD24AWG_PAD")
      (footprint "eagle-import:24AWG_PAD")
      (libsource (lib "eagle-import") (part "PAD24AWG_PAD"))
    )
    (comp (ref "SPI1_MOSI")
      (value "PAD24AWG_PAD")
      (footprint "eagle-import:24AWG_PAD")
      (libsource (lib "eagle-import") (part "PAD24AWG_PAD"))
    )
    (comp (ref "SPI1_SCLK")
      (value "PAD24AWG_PAD")
      (footprint "eagle-import:24AWG_PAD")
      (libsource (lib "eagle-import") (part "PAD24AWG_PAD"))
    )
    (comp (ref "U1")
      (value "MAX17504ATP+T")
      (footprint "eagle-import:21-0140L_T2055-4_MXM")
      (fields (field (name "COPYRIGHT") "Copyright (C) 2018 Accelerated Designs. All rights reserved"))
      (libsource (lib "eagle-import") (part "MAX17504ATP+T"))
    )
    (comp (ref "U2")
      (value "DMMT5401")
      (footprint "eagle-import:SOT26")
      (fields (field (name "MF") "Didoes Incorporated") (field (name "MPN") "DMMT5401-7-F"))
      (libsource (lib "eagle-import") (part "DMMT5401"))
    )
    (comp (ref "U3")
      (value "DMG2305UX")
      (footprint "eagle-import:SOT23")
      (fields (field (name "MF") "Diodes Incorporated") (field (name "MPN") "DMG2305UX-13"))
      (libsource (lib "eagle-import") (part "DMG2305UX"))
    )
    (comp (ref "U4")
      (value "STM32G474CEU6")
      (footprint "eagle-import:QFN50P700X700X60-49N")
      (fields (field (name "MOUSER_PART_NUMBER") "511-STM32G474CEU6") (field (name "MF") "ST"))
      (libsource (lib "eagle-import") (part "STM32G474CEU6"))
    )
    (comp (ref "U5")
      (value "TCAN334GSOT23")
      (footprint "eagle-import:SOT23-8")
      (fields (field (name "MF") "TI") (field (name "MPN") "TCAN334GDCNT"))
      (libsource (lib "eagle-import") (part "TCAN334GSOT23"))
    )
    (comp (ref "U6")
      (value "TCAN334GSOT23")
      (footprint "eagle-import:SOT23-8")
      (fields (field (name "MF") "TI") (field (name "MPN") "TCAN334GDCNT"))
      (libsource (lib "eagle-import") (part "TCAN334GSOT23"))
    )
    (comp (ref "U7")
      (value "STM32G474CEU6")
      (footprint "eagle-import:QFN50P700X700X60-49N")
      (fields (field (name "MOUSER_PART_NUMBER") "511-STM32G474CEU6") (field (name "MF") "ST"))
      (libsource (lib "eagle-import") (part "STM32G474CEU6"))
    )
    (comp (ref "U8")
      (value "BMI088LGA16")
      (footprint "eagle-import:LGA16")
      (fields (field (name "MF") "BOSCH") (field (name "MPN") "BMI088"))
      (libsource (lib "eagle-import") (part "BMI088LGA16"))
    )
    (comp (ref "U9")
      (value "LTC2875")
      (footprint "eagle-import:SOIC8")
      (fields (field (name "MF") "Analog") (field (name "MPN") "LTC2875IS8#PBF"))
      (libsource (lib "eagle-import") (part "LTC2875"))
    )
    (comp (ref "U10")
      (value "CAT24C32UDFN8")
      (footprint "eagle-import:UDFN8_2X3_ONS")
      (fields (field (name "MF") "ON Semiconductor") (field (name "MPN") "CAT24C32HU4I-GT3"))
      (libsource (lib "eagle-import") (part "CAT24C32UDFN8"))
    )
    (comp (ref "U11")
      (value "STM32G474CEU6")
      (footprint "eagle-import:QFN50P700X700X60-49N")
      (fields (field (name "MOUSER_PART_NUMBER") "511-STM32G474CEU6") (field (name "MF") "ST"))
      (libsource (lib "eagle-import") (part "STM32G474CEU6"))
    )
    (comp (ref "U12")
      (value "TCAN334GSOT23")
      (footprint "eagle-import:SOT23-8")
      (fields (field (name "MF") "TI") (field (name "MPN") "TCAN334GDCNT"))
      (libsource (lib "eagle-import") (part "TCAN334GSOT23"))
    )
    (comp (ref "U13")
      (value "TCAN334GSOT23")
      (footprint "eagle-import:SOT23-8")
      (fields (field (name "MF") "TI") (field (name "MPN") "TCAN334GDCNT"))
      (libsource (lib "eagle-import") (part "TCAN334GSOT23"))
    )
    (comp (ref "U14")
      (value "ICM-42688-P")
      (footprint "eagle-import:PQFN50P300X250X97-14N")
      (fields
        (field (name "DIGI-KEY_PART_NUMBER") "1428-ICM-42688-PCT-ND")
        (field (name "MF") "TDK InvenSense")
      )
      (libsource (lib "eagle-import") (part "ICM-42688-P"))
    )
    (comp (ref "V+")
      (value "PAD24AWG_PAD")
      (footprint "eagle-import:24AWG_PAD")
      (libsource (lib "eagle-import") (part "PAD24AWG_PAD"))
    )
  )
  (nets
    (net (code "1") (name "+3V3") (class "Default")
      (node (ref "3V3_TP") (pin "P$1") (pinfunction "P$1_P$1") (pintype "bidirectional"))
      (node (ref "C10") (pin "P$1") (pinfunction "P$1_P$1") (pintype "passive"))
      (node (ref "C11") (pin "P$1") (pinfunction "P$1_P$1") (pintype "passive"))
      (node (ref "C12") (pin "P$1") (pinfunction "P$1_P$1") (pintype "passive"))
      (node (ref "C13") (pin "P$1") (pinfunction "P$1_P$1") (pintype "passive"))
      (node (ref "C14") (pin "P$1") (pinfunction "P$1_P$1") (pintype "passive"))
      (node (ref "C15") (pin "P$1") (pinfunction "P$1_P$1") (pintype "passive"))
      (node (ref "C16") (pin "P$1") (pinfunction "P$1_P$1") (pintype "passive"))
      (node (ref "C17") (pin "P$1") (pinfunction "P$1_P$1") (pintype "passive"))
      (node (ref "C19") (pin "P$1") (pinfunction "P$1_P$1") (pintype "passive"))
      (node (ref "C20") (pin "P$1") (pinfunction "P$1_P$1") (pintype "passive"))
      (node (ref "C21") (pin "P$1") (pinfunction "P$1_P$1") (pintype "passive"))
      (node (ref "C22") (pin "P$1") (pinfunction "P$1_P$1") (pintype "passive"))
      (node (ref "C23") (pin "P$1") (pinfunction "P$1_P$1") (pintype "passive"))
      (node (ref "C24") (pin "P$1") (pinfunction "P$1_P$1") (pintype "passive"))
      (node (ref "C25") (pin "P$1") (pinfunction "P$1_P$1") (pintype "passive"))
      (node (ref "C27") (pin "P$1") (pinfunction "P$1_P$1") (pintype "passive"))
      (node (ref "C28") (pin "P$1") (pinfunction "P$1_P$1") (pintype "passive"))
      (node (ref "C29") (pin "P$1") (pinfunction "P$1_P$1") (pintype "passive"))
      (node (ref "C30") (pin "P$1") (pinfunction "P$1_P$1") (pintype "passive"))
      (node (ref "C31") (pin "P$1") (pinfunction "P$1_P$1") (pintype "passive"))
      (node (ref "C33") (pin "P$1") (pinfunction "P$1_P$1") (pintype "passive"))
      (node (ref "C34") (pin "P$1") (pinfunction "P$1_P$1") (pintype "passive"))
      (node (ref "C35") (pin "P$1") (pinfunction "P$1_P$1") (pintype "passive"))
      (node (ref "C36") (pin "P$1") (pinfunction "P$1_P$1") (pintype "passive"))
      (node (ref "C37") (pin "P$1") (pinfunction "P$1_P$1") (pintype "passive"))
      (node (ref "C38") (pin "P$1") (pinfunction "P$1_P$1") (pintype "passive"))
      (node (ref "C39") (pin "P$1") (pinfunction "P$1_P$1") (pintype "passive"))
      (node (ref "C40") (pin "P$1") (pinfunction "P$1_P$1") (pintype "passive"))
      (node (ref "C41") (pin "P$1") (pinfunction "P$1_P$1") (pintype "passive"))
      (node (ref "C42") (pin "P$1") (pinfunction "P$1_P$1") (pintype "passive"))
      (node (ref "J4") (pin "1") (pinfunction "1_1") (pintype "passive"))
      (node (ref "J4") (pin "17") (pinfunction "17_17") (pintype "passive"))
      (node (ref "JD1") (pin "6") (pinfunction "6_6") (pintype "passive"))
      (node (ref "JD2") (pin "6") (pinfunction "6_6") (pintype "passive"))
      (node (ref "JD3") (pin "6") (pinfunction "6_6") (pintype "passive"))
      (node (ref "JP6") (pin "2") (pinfunction "2_2") (pintype "passive"))
      (node (ref "L2") (pin "P$1") (pinfunction "P$1_P$1") (pintype "passive"))
      (node (ref "R11") (pin "P$1") (pinfunction "P$1_P$1") (pintype "passive"))
      (node (ref "R12") (pin "P$1") (pinfunction "P$1_P$1") (pintype "passive"))
      (node (ref "R14") (pin "P$1") (pinfunction "P$1_P$1") (pintype "passive"))
      (node (ref "R15") (pin "P$1") (pinfunction "P$1_P$1") (pintype "passive"))
      (node (ref "R16") (pin "P$1") (pinfunction "P$1_P$1") (pintype "passive"))
      (node (ref "R17") (pin "P$1") (pinfunction "P$1_P$1") (pintype "passive"))
      (node (ref "R18") (pin "P$1") (pinfunction "P$1_P$1") (pintype "passive"))
      (node (ref "R7") (pin "P$1") (pinfunction "P$1_P$1") (pintype "passive"))
      (node (ref "R8") (pin "P$1") (pinfunction "P$1_P$1") (pintype "passive"))
      (node (ref "U10") (pin "8") (pinfunction "VCC_8") (pintype "bidirectional"))
      (node (ref "U11") (pin "1") (pinfunction "VBAT_1") (pintype "bidirectional"))
      (node (ref "U11") (pin "20") (pinfunction "VREF+_20") (pintype "bidirectional"))
      (node (ref "U11") (pin "21") (pinfunction "VDDA_21") (pintype "bidirectional"))
      (node (ref "U11") (pin "23") (pinfunction "VDD_1_23") (pintype "bidirectional"))
      (node (ref "U11") (pin "35") (pinfunction "VDD_2_35") (pintype "bidirectional"))
      (node (ref "U11") (pin "4") (pinfunction "PC15-OSC32_OUT_4") (pintype "bidirectional"))
      (node (ref "U11") (pin "48") (pinfunction "VDD_3_48") (pintype "bidirectional"))
      (node (ref "U12") (pin "3") (pinfunction "VCC_3") (pintype "power_in"))
      (node (ref "U13") (pin "3") (pinfunction "VCC_3") (pintype "power_in"))
      (node (ref "U14") (pin "5") (pinfunction "VDDIO_5") (pintype "power_in"))
      (node (ref "U14") (pin "8") (pinfunction "VDD_8") (pintype "power_in"))
      (node (ref "U4") (pin "1") (pinfunction "VBAT_1") (pintype "bidirectional"))
      (node (ref "U4") (pin "20") (pinfunction "VREF+_20") (pintype "bidirectional"))
      (node (ref "U4") (pin "21") (pinfunction "VDDA_21") (pintype "bidirectional"))
      (node (ref "U4") (pin "23") (pinfunction "VDD_1_23") (pintype "bidirectional"))
      (node (ref "U4") (pin "35") (pinfunction "VDD_2_35") (pintype "bidirectional"))
      (node (ref "U4") (pin "48") (pinfunction "VDD_3_48") (pintype "bidirectional"))
      (node (ref "U5") (pin "3") (pinfunction "VCC_3") (pintype "power_in"))
      (node (ref "U6") (pin "3") (pinfunction "VCC_3") (pintype "power_in"))
      (node (ref "U7") (pin "1") (pinfunction "VBAT_1") (pintype "bidirectional"))
      (node (ref "U7") (pin "20") (pinfunction "VREF+_20") (pintype "bidirectional"))
      (node (ref "U7") (pin "21") (pinfunction "VDDA_21") (pintype "bidirectional"))
      (node (ref "U7") (pin "23") (pinfunction "VDD_1_23") (pintype "bidirectional"))
      (node (ref "U7") (pin "3") (pinfunction "PC14-OSC32_IN_3") (pintype "bidirectional"))
      (node (ref "U7") (pin "35") (pinfunction "VDD_2_35") (pintype "bidirectional"))
      (node (ref "U7") (pin "48") (pinfunction "VDD_3_48") (pintype "bidirectional"))
      (node (ref "U8") (pin "11") (pinfunction "VDDIO_11") (pintype "bidirectional"))
      (node (ref "U8") (pin "3") (pinfunction "VDD_3") (pintype "bidirectional"))
      (node (ref "U9") (pin "3") (pinfunction "VCC_3") (pintype "power_in"))
    )
    (net (code "2") (name "+5V") (class "Default")
      (node (ref "+5V") (pin "P$1") (pinfunction "P$1_P$1") (pintype "bidirectional"))
      (node (ref "J4") (pin "2") (pinfunction "2_2") (pintype "passive"))
      (node (ref "J4") (pin "4") (pinfunction "4_4") (pintype "passive"))
      (node (ref "JP6") (pin "1") (pinfunction "1_1") (pintype "passive"))
      (node (ref "R4") (pin "P$1") (pinfunction "P$1_P$1") (pintype "passive"))
      (node (ref "U2") (pin "6") (pinfunction "E1_6") (pintype "bidirectional"))
      (node (ref "U3") (pin "3") (pinfunction "D_3") (pintype "passive"))
    )
    (net (code "3") (name "/5VSW") (class "Default")
      (node (ref "C5") (pin "P$2") (pinfunction "P$2_P$2") (pintype "passive"))
      (node (ref "L1") (pin "2") (pinfunction "2_2") (pintype "passive"))
      (node (ref "U1") (pin "17") (pinfunction "LX_2_17") (pintype "passive"))
      (node (ref "U1") (pin "18") (pinfunction "LX_3_18") (pintype "passive"))
      (node (ref "U1") (pin "19") (pinfunction "LX_19") (pintype "passive"))
    )
    (net (code "4") (name "/AUX_IRQ1") (class "Default")
      (node (ref "J4") (pin "15") (pinfunction "15_15") (pintype "passive"))
      (node (ref "U7") (pin "17") (pinfunction "PB0_17") (pintype "bidirectional"))
    )
    (net (code "5") (name "/AUX_IRQ2") (class "Default")
      (node (ref "J4") (pin "16") (pinfunction "16_16") (pintype "passive"))
      (node (ref "U7") (pin "18") (pinfunction "PB1_18") (pintype "bidirectional"))
    )
    (net (code "6") (name "/AUX_IRQ3") (class "Default")
      (node (ref "J4") (pin "18") (pinfunction "18_18") (pintype "passive"))
      (node (ref "U7") (pin "19") (pinfunction "PB2_19") (pintype "bidirectional"))
    )
    (net (code "7") (name "/CAN_SHDN") (class "Default")
      (node (ref "U7") (pin "29") (pinfunction "PC6_29") (pintype "bidirectional"))
      (node (ref "U9") (pin "8") (pinfunction "RS_8") (pintype "input"))
    )
    (net (code "8") (name "/I2C1_SCL") (class "Default")
      (node (ref "J4") (pin "5") (pinfunction "5_5") (pintype "passive"))
    )
    (net (code "9") (name "/I2C1_SDA") (class "Default")
      (node (ref "J4") (pin "3") (pinfunction "3_3") (pintype "passive"))
    )
    (net (code "10") (name "/ID_SCL") (class "Default")
      (node (ref "J4") (pin "28") (pinfunction "28_28") (pintype "passive"))
      (node (ref "R16") (pin "P$2") (pinfunction "P$2_P$2") (pintype "passive"))
      (node (ref "U10") (pin "6") (pinfunction "SCL_6") (pintype "bidirectional"))
    )
    (net (code "11") (name "/ID_SDA") (class "Default")
      (node (ref "J4") (pin "27") (pinfunction "27_27") (pintype "passive"))
      (node (ref "R15") (pin "P$2") (pinfunction "P$2_P$2") (pintype "passive"))
      (node (ref "U10") (pin "5") (pinfunction "SDA_5") (pintype "bidirectional"))
    )
    (net (code "12") (name "/IFACEA_IRQ1") (class "Default")
      (node (ref "J4") (pin "37") (pinfunction "37_37") (pintype "passive"))
      (node (ref "U4") (pin "17") (pinfunction "PB0_17") (pintype "bidirectional"))
    )
    (net (code "13") (name "/IFACEB_IRQ1") (class "Default")
      (node (ref "J4") (pin "29") (pinfunction "29_29") (pintype "passive"))
      (node (ref "U11") (pin "17") (pinfunction "PB0_17") (pintype "bidirectional"))
    )
    (net (code "14") (name "/IMU2_CLKIN") (class "Default")
      (node (ref "U14") (pin "9") (pinfunction "INT2/FSYNC/CLKIN_9") (pintype "bidirectional"))
      (node (ref "U7") (pin "22") (pinfunction "PB10_22") (pintype "bidirectional"))
    )
    (net (code "15") (name "/IMU2_CS") (class "Default")
      (node (ref "U14") (pin "12") (pinfunction "AP_CS_12") (pintype "input"))
      (node (ref "U7") (pin "24") (pinfunction "PB11_24") (pintype "bidirectional"))
    )
    (net (code "16") (name "/IMU_ACC_INT") (class "Default")
      (node (ref "U7") (pin "32") (pinfunction "PA10_32") (pintype "bidirectional"))
      (node (ref "U8") (pin "16") (pinfunction "INT1_16") (pintype "bidirectional"))
    )
    (net (code "17") (name "/IMU_CS1") (class "Default")
      (node (ref "U7") (pin "31") (pinfunction "PA9_31") (pintype "bidirectional"))
      (node (ref "U8") (pin "14") (pinfunction "CSB1_14") (pintype "bidirectional"))
    )
    (net (code "18") (name "/IMU_CS2") (class "Default")
      (node (ref "U7") (pin "25") (pinfunction "PB12_25") (pintype "bidirectional"))
      (node (ref "U8") (pin "5") (pinfunction "CSB2_5") (pintype "bidirectional"))
    )
    (net (code "19") (name "/IMU_GYRO_INT") (class "Default")
      (node (ref "U14") (pin "4") (pinfunction "INT1/INT_4") (pintype "output"))
      (node (ref "U7") (pin "30") (pinfunction "PA8_30") (pintype "bidirectional"))
      (node (ref "U8") (pin "12") (pinfunction "INT3_12") (pintype "bidirectional"))
    )
    (net (code "20") (name "/IMU_MISO") (class "Default")
      (node (ref "U14") (pin "1") (pinfunction "AP_SDO/AP_AD0_1") (pintype "bidirectional"))
      (node (ref "U7") (pin "27") (pinfunction "PB14_27") (pintype "bidirectional"))
      (node (ref "U8") (pin "10") (pinfunction "SDO2_10") (pintype "bidirectional"))
      (node (ref "U8") (pin "15") (pinfunction "SDO1_15") (pintype "bidirectional"))
    )
    (net (code "21") (name "/IMU_MOSI") (class "Default")
      (node (ref "U14") (pin "14") (pinfunction "AP_SDA/AP_SDIO/AP_SDI_14") (pintype "bidirectional"))
      (node (ref "U7") (pin "28") (pinfunction "PB15_28") (pintype "bidirectional"))
      (node (ref "U8") (pin "9") (pinfunction "SDI_9") (pintype "bidirectional"))
    )
    (net (code "22") (name "/IMU_SCK") (class "Default")
      (node (ref "U14") (pin "13") (pinfunction "AP_SCL/AP_SCLK_13") (pintype "input"))
      (node (ref "U7") (pin "26") (pinfunction "PB13_26") (pintype "bidirectional"))
      (node (ref "U8") (pin "8") (pinfunction "SCK_8") (pintype "bidirectional"))
    )
    (net (code "23") (name "/NRF_CE") (class "Default")
      (node (ref "J3") (pin "6") (pinfunction "6_6") (pintype "passive"))
      (node (ref "U7") (pin "44") (pinfunction "PB6_44") (pintype "bidirectional"))
    )
    (net (code "24") (name "/NRF_CS") (class "Default")
      (node (ref "J3") (pin "5") (pinfunction "5_5") (pintype "passive"))
      (node (ref "U7") (pin "38") (pinfunction "PA15_38") (pintype "bidirectional"))
    )
    (net (code "25") (name "/NRF_IRQ") (class "Default")
      (node (ref "J3") (pin "1") (pinfunction "1_1") (pintype "passive"))
      (node (ref "U7") (pin "45") (pinfunction "PB7_45") (pintype "bidirectional"))
    )
    (net (code "26") (name "/NRF_MISO") (class "Default")
      (node (ref "J3") (pin "2") (pinfunction "2_2") (pintype "passive"))
      (node (ref "U7") (pin "42") (pinfunction "PB4_42") (pintype "bidirectional"))
    )
    (net (code "27") (name "/NRF_MOSI") (class "Default")
      (node (ref "J3") (pin "3") (pinfunction "3_3") (pintype "passive"))
      (node (ref "U7") (pin "43") (pinfunction "PB5_43") (pintype "bidirectional"))
    )
    (net (code "28") (name "/NRF_SCK") (class "Default")
      (node (ref "J3") (pin "4") (pinfunction "4_4") (pintype "passive"))
      (node (ref "U7") (pin "41") (pinfunction "PB3_41") (pintype "bidirectional"))
    )
    (net (code "29") (name "/PI32") (class "Default")
      (node (ref "J4") (pin "32") (pinfunction "32_32") (pintype "passive"))
      (node (ref "JP5") (pin "1") (pinfunction "1_1") (pintype "passive"))
    )
    (net (code "30") (name "/PI33") (class "Default")
      (node (ref "J4") (pin "33") (pinfunction "33_33") (pintype "passive"))
      (node (ref "JP5") (pin "2") (pinfunction "2_2") (pintype "passive"))
    )
    (net (code "31") (name "/PI_RX_3V") (class "Default")
      (node (ref "J4") (pin "10") (pinfunction "10_10") (pintype "passive"))
    )
    (net (code "32") (name "/PI_TX_3V") (class "Default")
      (node (ref "J4") (pin "8") (pinfunction "8_8") (pintype "passive"))
    )
    (net (code "33") (name "/REGOUT") (class "Default")
      (node (ref "C7") (pin "P$1") (pinfunction "P$1_P$1") (pintype "passive"))
      (node (ref "C8") (pin "P$1") (pinfunction "P$1_P$1") (pintype "passive"))
      (node (ref "L1") (pin "1") (pinfunction "1_1") (pintype "passive"))
      (node (ref "R2") (pin "P$1") (pinfunction "P$1_P$1") (pintype "passive"))
      (node (ref "REGOUT") (pin "P$1") (pinfunction "P$1_P$1") (pintype "bidirectional"))
      (node (ref "U2") (pin "5") (pinfunction "E2_5") (pintype "bidirectional"))
      (node (ref "U3") (pin "2") (pinfunction "S_2") (pintype "passive"))
    )
    (net (code "34") (name "/SPI0_CS0") (class "Default")
      (node (ref "J4") (pin "24") (pinfunction "24_24") (pintype "passive"))
      (node (ref "SPI0_CS0") (pin "P$1") (pinfunction "P$1_P$1") (pintype "bidirectional"))
      (node (ref "U7") (pin "12") (pinfunction "PA4_12") (pintype "bidirectional"))
    )
    (net (code "35") (name "/SPI0_CS1") (class "Default")
      (node (ref "J4") (pin "26") (pinfunction "26_26") (pintype "passive"))
    )
    (net (code "36") (name "/SPI0_MISO") (class "Default")
      (node (ref "J4") (pin "21") (pinfunction "21_21") (pintype "passive"))
      (node (ref "SPI0_MISO") (pin "P$1") (pinfunction "P$1_P$1") (pintype "bidirectional"))
      (node (ref "U7") (pin "14") (pinfunction "PA6_14") (pintype "bidirectional"))
    )
    (net (code "37") (name "/SPI0_MOSI") (class "Default")
      (node (ref "J4") (pin "19") (pinfunction "19_19") (pintype "passive"))
      (node (ref "SPI0_MOSI") (pin "P$1") (pinfunction "P$1_P$1") (pintype "bidirectional"))
      (node (ref "U7") (pin "15") (pinfunction "PA7_15") (pintype "bidirectional"))
    )
    (net (code "38") (name "/SPI0_SCLK") (class "Default")
      (node (ref "J4") (pin "23") (pinfunction "23_23") (pintype "passive"))
      (node (ref "SPI0_SCLK") (pin "P$1") (pinfunction "P$1_P$1") (pintype "bidirectional"))
      (node (ref "U7") (pin "13") (pinfunction "PA5_13") (pintype "bidirectional"))
    )
    (net (code "39") (name "/SPI1_CS0") (class "Default")
      (node (ref "J4") (pin "12") (pinfunction "12_12") (pintype "passive"))
      (node (ref "SPI1_CS0") (pin "P$1") (pinfunction "P$1_P$1") (pintype "bidirectional"))
      (node (ref "U4") (pin "12") (pinfunction "PA4_12") (pintype "bidirectional"))
    )
    (net (code "40") (name "/SPI1_CS1") (class "Default")
      (node (ref "J4") (pin "11") (pinfunction "11_11") (pintype "passive"))
      (node (ref "SPI1_CS1") (pin "P$1") (pinfunction "P$1_P$1") (pintype "bidirectional"))
      (node (ref "U11") (pin "12") (pinfunction "PA4_12") (pintype "bidirectional"))
    )
    (net (code "41") (name "/SPI1_CS2") (class "Default")
      (node (ref "J4") (pin "36") (pinfunction "36_36") (pintype "passive"))
    )
    (net (code "42") (name "/SPI1_MISO") (class "Default")
      (node (ref "J4") (pin "35") (pinfunction "35_35") (pintype "passive"))
      (node (ref "SPI1_MISO") (pin "P$1") (pinfunction "P$1_P$1") (pintype "bidirectional"))
      (node (ref "U11") (pin "14") (pinfunction "PA6_14") (pintype "bidirectional"))
      (node (ref "U4") (pin "14") (pinfunction "PA6_14") (pintype "bidirectional"))
    )
    (net (code "43") (name "/SPI1_MOSI") (class "Default")
      (node (ref "J4") (pin "38") (pinfunction "38_38") (pintype "passive"))
      (node (ref "SPI1_MOSI") (pin "P$1") (pinfunction "P$1_P$1") (pintype "bidirectional"))
      (node (ref "U11") (pin "15") (pinfunction "PA7_15") (pintype "bidirectional"))
      (node (ref "U4") (pin "15") (pinfunction "PA7_15") (pintype "bidirectional"))
    )
    (net (code "44") (name "/SPI1_SCLK") (class "Default")
      (node (ref "J4") (pin "40") (pinfunction "40_40") (pintype "passive"))
      (node (ref "SPI1_SCLK") (pin "P$1") (pinfunction "P$1_P$1") (pintype "bidirectional"))
      (node (ref "U11") (pin "13") (pinfunction "PA5_13") (pintype "bidirectional"))
      (node (ref "U4") (pin "13") (pinfunction "PA5_13") (pintype "bidirectional"))
    )
    (net (code "45") (name "/V+") (class "Default")
      (node (ref "F1") (pin "1") (pinfunction "1_1") (pintype "passive"))
      (node (ref "J1") (pin "2") (pinfunction "2_2") (pintype "passive"))
      (node (ref "J2") (pin "2") (pinfunction "2_2") (pintype "passive"))
      (node (ref "R21") (pin "P$1") (pinfunction "P$1_P$1") (pintype "passive"))
      (node (ref "V+") (pin "P$1") (pinfunction "P$1_P$1") (pintype "bidirectional"))
    )
    (net (code "46") (name "/V+FUSED") (class "Default")
      (node (ref "C1") (pin "P$1") (pinfunction "P$1_P$1") (pintype "passive"))
      (node (ref "C2") (pin "P$1") (pinfunction "P$1_P$1") (pintype "passive"))
      (node (ref "C3") (pin "P$1") (pinfunction "P$1_P$1") (pintype "passive"))
      (node (ref "D8") (pin "C") (pinfunction "C_C") (pintype "bidirectional"))
      (node (ref "F1") (pin "2") (pinfunction "2_2") (pintype "passive"))
      (node (ref "U1") (pin "1") (pinfunction "VIN_2_1") (pintype "passive"))
      (node (ref "U1") (pin "2") (pinfunction "VIN_3_2") (pintype "passive"))
      (node (ref "U1") (pin "3") (pinfunction "VIN_3") (pintype "passive"))
      (node (ref "U1") (pin "4") (pinfunction "EN/UVLO_4") (pintype "passive"))
    )
    (net (code "47") (name "/V+SENSE") (class "Default")
      (node (ref "R1") (pin "P$1") (pinfunction "P$1_P$1") (pintype "passive"))
      (node (ref "R21") (pin "P$2") (pinfunction "P$2_P$2") (pintype "passive"))
      (node (ref "U7") (pin "16") (pinfunction "PC4_16") (pintype "bidirectional"))
    )
    (net (code "48") (name "GND") (class "Default")
      (node (ref "C1") (pin "P$2") (pinfunction "P$2_P$2") (pintype "passive"))
      (node (ref "C10") (pin "P$2") (pinfunction "P$2_P$2") (pintype "passive"))
      (node (ref "C11") (pin "P$2") (pinfunction "P$2_P$2") (pintype "passive"))
      (node (ref "C12") (pin "P$2") (pinfunction "P$2_P$2") (pintype "passive"))
      (node (ref "C13") (pin "P$2") (pinfunction "P$2_P$2") (pintype "passive"))
      (node (ref "C14") (pin "P$2") (pinfunction "P$2_P$2") (pintype "passive"))
      (node (ref "C15") (pin "P$2") (pinfunction "P$2_P$2") (pintype "passive"))
      (node (ref "C16") (pin "P$2") (pinfunction "P$2_P$2") (pintype "passive"))
      (node (ref "C17") (pin "P$2") (pinfunction "P$2_P$2") (pintype "passive"))
      (node (ref "C18") (pin "P$2") (pinfunction "P$2_P$2") (pintype "passive"))
      (node (ref "C19") (pin "P$2") (pinfunction "P$2_P$2") (pintype "passive"))
      (node (ref "C2") (pin "P$2") (pinfunction "P$2_P$2") (pintype "passive"))
      (node (ref "C20") (pin "P$2") (pinfunction "P$2_P$2") (pintype "passive"))
      (node (ref "C21") (pin "P$2") (pinfunction "P$2_P$2") (pintype "passive"))
      (node (ref "C22") (pin "P$2") (pinfunction "P$2_P$2") (pintype "passive"))
      (node (ref "C23") (pin "P$2") (pinfunction "P$2_P$2") (pintype "passive"))
      (node (ref "C24") (pin "P$2") (pinfunction "P$2_P$2") (pintype "passive"))
      (node (ref "C25") (pin "P$2") (pinfunction "P$2_P$2") (pintype "passive"))
      (node (ref "C26") (pin "P$2") (pinfunction "P$2_P$2") (pintype "passive"))
      (node (ref "C27") (pin "P$2") (pinfunction "P$2_P$2") (pintype "passive"))
      (node (ref "C28") (pin "P$2") (pinfunction "P$2_P$2") (pintype "passive"))
      (node (ref "C29") (pin "P$2") (pinfunction "P$2_P$2") (pintype "passive"))
      (node (ref "C3") (pin "P$2") (pinfunction "P$2_P$2") (pintype "passive"))
      (node (ref "C30") (pin "P$2") (pinfunction "P$2_P$2") (pintype "passive"))
      (node (ref "C31") (pin "P$2") (pinfunction "P$2_P$2") (pintype "passive"))
      (node (ref "C32") (pin "P$2") (pinfunction "P$2_P$2") (pintype "passive"))
      (node (ref "C33") (pin "P$2") (pinfunction "P$2_P$2") (pintype "passive"))
      (node (ref "C34") (pin "P$2") (pinfunction "P$2_P$2") (pintype "passive"))
      (node (ref "C35") (pin "P$2") (pinfunction "P$2_P$2") (pintype "passive"))
      (node (ref "C36") (pin "P$2") (pinfunction "P$2_P$2") (pintype "passive"))
      (node (ref "C37") (pin "P$2") (pinfunction "P$2_P$2") (pintype "passive"))
      (node (ref "C38") (pin "P$2") (pinfunction "P$2_P$2") (pintype "passive"))
      (node (ref "C39") (pin "P$2") (pinfunction "P$2_P$2") (pintype "passive"))
      (node (ref "C4") (pin "P$2") (pinfunction "P$2_P$2") (pintype "passive"))
      (node (ref "C40") (pin "P$2") (pinfunction "P$2_P$2") (pintype "passive"))
      (node (ref "C41") (pin "P$2") (pinfunction "P$2_P$2") (pintype "passive"))
      (node (ref "C42") (pin "P$2") (pinfunction "P$2_P$2") (pintype "passive"))
      (node (ref "C43") (pin "P$2") (pinfunction "P$2_P$2") (pintype "passive"))
      (node (ref "C6") (pin "P$2") (pinfunction "P$2_P$2") (pintype "passive"))
      (node (ref "C7") (pin "P$2") (pinfunction "P$2_P$2") (pintype "passive"))
      (node (ref "C8") (pin "P$2") (pinfunction "P$2_P$2") (pintype "passive"))
      (node (ref "C9") (pin "P$2") (pinfunction "P$2_P$2") (pintype "passive"))
      (node (ref "D1") (pin "CATHODE") (pinfunction "CATHODE_CATHODE") (pintype "power_in"))
      (node (ref "D8") (pin "A") (pinfunction "A_A") (pintype "bidirectional"))
      (node (ref "GND") (pin "P$1") (pinfunction "P$1_P$1") (pintype "bidirectional"))
      (node (ref "J1") (pin "1") (pinfunction "1_1") (pintype "passive"))
      (node (ref "J2") (pin "1") (pinfunction "1_1") (pintype "passive"))
      (node (ref "J3") (pin "8") (pinfunction "8_8") (pintype "passive"))
      (node (ref "J4") (pin "14") (pinfunction "14_14") (pintype "passive"))
      (node (ref "J4") (pin "20") (pinfunction "20_20") (pintype "passive"))
      (node (ref "J4") (pin "25") (pinfunction "25_25") (pintype "passive"))
      (node (ref "J4") (pin "30") (pinfunction "30_30") (pintype "passive"))
      (node (ref "J4") (pin "34") (pinfunction "34_34") (pintype "passive"))
      (node (ref "J4") (pin "39") (pinfunction "39_39") (pintype "passive"))
      (node (ref "J4") (pin "6") (pinfunction "6_6") (pintype "passive"))
      (node (ref "J4") (pin "9") (pinfunction "9_9") (pintype "passive"))
      (node (ref "JC1") (pin "3") (pinfunction "3_3") (pintype "passive"))
      (node (ref "JC2") (pin "3") (pinfunction "3_3") (pintype "passive"))
      (node (ref "JC3") (pin "3") (pinfunction "3_3") (pintype "passive"))
      (node (ref "JC4") (pin "3") (pinfunction "3_3") (pintype "passive"))
      (node (ref "JC5") (pin "3") (pinfunction "3_3") (pintype "passive"))
      (node (ref "JD1") (pin "4") (pinfunction "4_4") (pintype "passive"))
      (node (ref "JD2") (pin "4") (pinfunction "4_4") (pintype "passive"))
      (node (ref "JD3") (pin "4") (pinfunction "4_4") (pintype "passive"))
      (node (ref "JP2") (pin "1") (pinfunction "1_1") (pintype "passive"))
      (node (ref "JP3") (pin "3") (pinfunction "3_3") (pintype "passive"))
      (node (ref "JP4") (pin "3") (pinfunction "3_3") (pintype "passive"))
      (node (ref "JP5") (pin "3") (pinfunction "3_3") (pintype "passive"))
      (node (ref "JP6") (pin "3") (pinfunction "3_3") (pintype "passive"))
      (node (ref "JP7") (pin "1") (pinfunction "1_1") (pintype "passive"))
      (node (ref "R1") (pin "P$2") (pinfunction "P$2_P$2") (pintype "passive"))
      (node (ref "R3") (pin "P$2") (pinfunction "P$2_P$2") (pintype "passive"))
      (node (ref "R5") (pin "P$2") (pinfunction "P$2_P$2") (pintype "passive"))
      (node (ref "R6") (pin "P$2") (pinfunction "P$2_P$2") (pintype "passive"))
      (node (ref "U1") (pin "13") (pinfunction "SGND_13") (pintype "passive"))
      (node (ref "U1") (pin "14") (pinfunction "PGND_2_14") (pintype "passive"))
      (node (ref "U1") (pin "15") (pinfunction "PGND_3_15") (pintype "passive"))
      (node (ref "U1") (pin "16") (pinfunction "PGND_16") (pintype "passive"))
      (node (ref "U1") (pin "21") (pinfunction "EPAD_21") (pintype "passive"))
      (node (ref "U1") (pin "22") (pinfunction "EPAD_22") (pintype "passive"))
      (node (ref "U1") (pin "23") (pinfunction "EPAD_23") (pintype "passive"))
      (node (ref "U1") (pin "24") (pinfunction "EPAD_24") (pintype "passive"))
      (node (ref "U1") (pin "25") (pinfunction "EPAD_25") (pintype "passive"))
      (node (ref "U1") (pin "26") (pinfunction "EPAD_26") (pintype "passive"))
      (node (ref "U1") (pin "27") (pinfunction "EPAD_27") (pintype "passive"))
      (node (ref "U1") (pin "28") (pinfunction "EPAD_28") (pintype "passive"))
      (node (ref "U1") (pin "29") (pinfunction "EPAD_29") (pintype "passive"))
      (node (ref "U1") (pin "30") (pinfunction "EPAD_30") (pintype "passive"))
      (node (ref "U10") (pin "1") (pinfunction "A0_1") (pintype "bidirectional"))
      (node (ref "U10") (pin "2") (pinfunction "A1_2") (pintype "bidirectional"))
      (node (ref "U10") (pin "3") (pinfunction "A2_3") (pintype "bidirectional"))
      (node (ref "U10") (pin "4") (pinfunction "VSS_4") (pintype "bidirectional"))
      (node (ref "U11") (pin "3") (pinfunction "PC14-OSC32_IN_3") (pintype "bidirectional"))
      (node (ref "U11") (pin "49") (pinfunction "THERMALPAD_49") (pintype "bidirectional"))
      (node (ref "U12") (pin "2") (pinfunction "GND_2") (pintype "power_in"))
      (node (ref "U12") (pin "5") (pinfunction "SHDN_5") (pintype "input"))
      (node (ref "U12") (pin "8") (pinfunction "STB_8") (pintype "input"))
      (node (ref "U13") (pin "2") (pinfunction "GND_2") (pintype "power_in"))
      (node (ref "U13") (pin "5") (pinfunction "SHDN_5") (pintype "input"))
      (node (ref "U13") (pin "8") (pinfunction "STB_8") (pintype "input"))
      (node (ref "U14") (pin "6") (pinfunction "GND_6") (pintype "power_in"))
      (node (ref "U4") (pin "3") (pinfunction "PC14-OSC32_IN_3") (pintype "bidirectional"))
      (node (ref "U4") (pin "4") (pinfunction "PC15-OSC32_OUT_4") (pintype "bidirectional"))
      (node (ref "U4") (pin "49") (pinfunction "THERMALPAD_49") (pintype "bidirectional"))
      (node (ref "U5") (pin "2") (pinfunction "GND_2") (pintype "power_in"))
      (node (ref "U5") (pin "5") (pinfunction "SHDN_5") (pintype "input"))
      (node (ref "U5") (pin "8") (pinfunction "STB_8") (pintype "input"))
      (node (ref "U6") (pin "2") (pinfunction "GND_2") (pintype "power_in"))
      (node (ref "U6") (pin "5") (pinfunction "SHDN_5") (pintype "input"))
      (node (ref "U6") (pin "8") (pinfunction "STB_8") (pintype "input"))
      (node (ref "U7") (pin "4") (pinfunction "PC15-OSC32_OUT_4") (pintype "bidirectional"))
      (node (ref "U7") (pin "49") (pinfunction "THERMALPAD_49") (pintype "bidirectional"))
      (node (ref "U8") (pin "4") (pinfunction "GND_4") (pintype "bidirectional"))
      (node (ref "U8") (pin "6") (pinfunction "GNDIO_6") (pintype "bidirectional"))
      (node (ref "U8") (pin "7") (pinfunction "PS_7") (pintype "bidirectional"))
      (node (ref "U9") (pin "2") (pinfunction "GND_2") (pintype "power_in"))
    )
    (net (code "49") (name "Net-(C26-PadP$1)") (class "Default")
      (node (ref "C26") (pin "P$1") (pinfunction "P$1_P$1") (pintype "passive"))
      (node (ref "C43") (pin "P$1") (pinfunction "P$1_P$1") (pintype "passive"))
      (node (ref "J3") (pin "7") (pinfunction "7_7") (pintype "passive"))
      (node (ref "L2") (pin "P$2") (pinfunction "P$2_P$2") (pintype "passive"))
    )
    (net (code "50") (name "Net-(D1-PadANODE)") (class "Default")
      (node (ref "D1") (pin "ANODE") (pinfunction "ANODE_ANODE") (pintype "power_in"))
      (node (ref "R4") (pin "P$2") (pinfunction "P$2_P$2") (pintype "passive"))
    )
    (net (code "51") (name "Net-(D2-PadANODE)") (class "Default")
      (node (ref "D2") (pin "ANODE") (pinfunction "ANODE_ANODE") (pintype "power_in"))
      (node (ref "R7") (pin "P$2") (pinfunction "P$2_P$2") (pintype "passive"))
    )
    (net (code "52") (name "Net-(D3-PadANODE)") (class "Default")
      (node (ref "D3") (pin "ANODE") (pinfunction "ANODE_ANODE") (pintype "power_in"))
      (node (ref "R8") (pin "P$2") (pinfunction "P$2_P$2") (pintype "passive"))
    )
    (net (code "53") (name "Net-(D4-PadANODE)") (class "Default")
      (node (ref "D4") (pin "ANODE") (pinfunction "ANODE_ANODE") (pintype "power_in"))
      (node (ref "R11") (pin "P$2") (pinfunction "P$2_P$2") (pintype "passive"))
    )
    (net (code "54") (name "Net-(D5-PadANODE)") (class "Default")
      (node (ref "D5") (pin "ANODE") (pinfunction "ANODE_ANODE") (pintype "power_in"))
      (node (ref "R12") (pin "P$2") (pinfunction "P$2_P$2") (pintype "passive"))
    )
    (net (code "55") (name "Net-(D6-PadANODE)") (class "Default")
      (node (ref "D6") (pin "ANODE") (pinfunction "ANODE_ANODE") (pintype "power_in"))
      (node (ref "R17") (pin "P$2") (pinfunction "P$2_P$2") (pintype "passive"))
    )
    (net (code "56") (name "Net-(D7-PadANODE)") (class "Default")
      (node (ref "D7") (pin "ANODE") (pinfunction "ANODE_ANODE") (pintype "power_in"))
      (node (ref "R18") (pin "P$2") (pinfunction "P$2_P$2") (pintype "passive"))
    )
    (net (code "57") (name "Net-(U1-BST)") (class "Default")
      (node (ref "C5") (pin "P$1") (pinfunction "P$1_P$1") (pintype "passive"))
      (node (ref "U1") (pin "20") (pinfunction "BST_20") (pintype "passive"))
    )
    (net (code "58") (name "Net-(U1-FB)") (class "Default")
      (node (ref "R2") (pin "P$2") (pinfunction "P$2_P$2") (pintype "passive"))
      (node (ref "R3") (pin "P$1") (pinfunction "P$1_P$1") (pintype "passive"))
      (node (ref "U1") (pin "9") (pinfunction "FB_9") (pintype "passive"))
    )
    (net (code "59") (name "Net-(U1-SS)") (class "Default")
      (node (ref "C4") (pin "P$1") (pinfunction "P$1_P$1") (pintype "passive"))
      (node (ref "U1") (pin "7") (pinfunction "SS_7") (pintype "passive"))
    )
    (net (code "60") (name "Net-(U1-VCC)") (class "Default")
      (node (ref "C6") (pin "P$1") (pinfunction "P$1_P$1") (pintype "passive"))
      (node (ref "U1") (pin "12") (pinfunction "VCC_12") (pintype "power_in"))
    )
    (net (code "61") (name "Net-(U2-B1)") (class "Default")
      (node (ref "R5") (pin "P$1") (pinfunction "P$1_P$1") (pintype "passive"))
      (node (ref "U2") (pin "2") (pinfunction "B1_2") (pintype "bidirectional"))
      (node (ref "U2") (pin "3") (pinfunction "B2_3") (pintype "bidirectional"))
      (node (ref "U2") (pin "4") (pinfunction "C2_4") (pintype "bidirectional"))
    )
    (net (code "62") (name "Net-(U2-C1)") (class "Default")
      (node (ref "R6") (pin "P$1") (pinfunction "P$1_P$1") (pintype "passive"))
      (node (ref "U2") (pin "1") (pinfunction "C1_1") (pintype "bidirectional"))
      (node (ref "U3") (pin "1") (pinfunction "G_1") (pintype "passive"))
    )
    (net (code "63") (name "Net-(U4-PA11)") (class "Default")
      (node (ref "U4") (pin "33") (pinfunction "PA11_33") (pintype "bidirectional"))
      (node (ref "U6") (pin "4") (pinfunction "RXD_4") (pintype "output"))
    )
    (net (code "64") (name "Net-(U4-PA12)") (class "Default")
      (node (ref "U4") (pin "34") (pinfunction "PA12_34") (pintype "bidirectional"))
      (node (ref "U6") (pin "1") (pinfunction "TXD_1") (pintype "input"))
    )
    (net (code "65") (name "Net-(U4-PA13)") (class "Default")
      (node (ref "JD1") (pin "3") (pinfunction "3_3") (pintype "passive"))
      (node (ref "U4") (pin "36") (pinfunction "PA13_36") (pintype "bidirectional"))
    )
    (net (code "66") (name "Net-(U4-PA14)") (class "Default")
      (node (ref "JD1") (pin "5") (pinfunction "5_5") (pintype "passive"))
      (node (ref "U4") (pin "37") (pinfunction "PA14_37") (pintype "bidirectional"))
    )
    (net (code "67") (name "Net-(U4-PB3)") (class "Default")
      (node (ref "U4") (pin "41") (pinfunction "PB3_41") (pintype "bidirectional"))
      (node (ref "U5") (pin "4") (pinfunction "RXD_4") (pintype "output"))
    )
    (net (code "68") (name "Net-(U4-PB4)") (class "Default")
      (node (ref "U4") (pin "42") (pinfunction "PB4_42") (pintype "bidirectional"))
      (node (ref "U5") (pin "1") (pinfunction "TXD_1") (pintype "input"))
    )
    (net (code "69") (name "Net-(U4-PB12)") (class "Default")
      (node (ref "JP4") (pin "2") (pinfunction "2_2") (pintype "passive"))
      (node (ref "U4") (pin "25") (pinfunction "PB12_25") (pintype "bidirectional"))
    )
    (net (code "70") (name "Net-(U4-PB13)") (class "Default")
      (node (ref "JP4") (pin "1") (pinfunction "1_1") (pintype "passive"))
      (node (ref "U4") (pin "26") (pinfunction "PB13_26") (pintype "bidirectional"))
    )
    (net (code "71") (name "Net-(U4-PF0-OSC_IN)") (class "Default")
      (node (ref "D3") (pin "CATHODE") (pinfunction "CATHODE_CATHODE") (pintype "power_in"))
      (node (ref "U4") (pin "5") (pinfunction "PF0-OSC_IN_5") (pintype "bidirectional"))
    )
    (net (code "72") (name "Net-(U4-PF1-OSC_OUT)") (class "Default")
      (node (ref "D2") (pin "CATHODE") (pinfunction "CATHODE_CATHODE") (pintype "power_in"))
      (node (ref "U4") (pin "6") (pinfunction "PF1-OSC_OUT_6") (pintype "bidirectional"))
    )
    (net (code "73") (name "Net-(U4-PG10-NRST)") (class "Default")
      (node (ref "C9") (pin "P$1") (pinfunction "P$1_P$1") (pintype "passive"))
      (node (ref "JD1") (pin "2") (pinfunction "2_2") (pintype "passive"))
      (node (ref "U4") (pin "7") (pinfunction "PG10-NRST_7") (pintype "bidirectional"))
    )
    (net (code "74") (name "Net-(U5-CANH)") (class "Default")
      (node (ref "JC1") (pin "1") (pinfunction "1_1") (pintype "passive"))
      (node (ref "R9") (pin "P$1") (pinfunction "P$1_P$1") (pintype "passive"))
      (node (ref "U5") (pin "7") (pinfunction "CANH_7") (pintype "bidirectional"))
    )
    (net (code "75") (name "Net-(U5-CANL)") (class "Default")
      (node (ref "JC1") (pin "2") (pinfunction "2_2") (pintype "passive"))
      (node (ref "R9") (pin "P$2") (pinfunction "P$2_P$2") (pintype "passive"))
      (node (ref "U5") (pin "6") (pinfunction "CANL_6") (pintype "bidirectional"))
    )
    (net (code "76") (name "Net-(U6-CANH)") (class "Default")
      (node (ref "JC2") (pin "1") (pinfunction "1_1") (pintype "passive"))
      (node (ref "R10") (pin "P$1") (pinfunction "P$1_P$1") (pintype "passive"))
      (node (ref "U6") (pin "7") (pinfunction "CANH_7") (pintype "bidirectional"))
    )
    (net (code "77") (name "Net-(U6-CANL)") (class "Default")
      (node (ref "JC2") (pin "2") (pinfunction "2_2") (pintype "passive"))
      (node (ref "R10") (pin "P$2") (pinfunction "P$2_P$2") (pintype "passive"))
      (node (ref "U6") (pin "6") (pinfunction "CANL_6") (pintype "bidirectional"))
    )
    (net (code "78") (name "Net-(U7-PA0)") (class "Default")
      (node (ref "JP2") (pin "5") (pinfunction "5_5") (pintype "passive"))
      (node (ref "U7") (pin "8") (pinfunction "PA0_8") (pintype "bidirectional"))
    )
    (net (code "79") (name "Net-(U7-PA1)") (class "Default")
      (node (ref "JP2") (pin "4") (pinfunction "4_4") (pintype "passive"))
      (node (ref "U7") (pin "9") (pinfunction "PA1_9") (pintype "bidirectional"))
    )
    (net (code "80") (name "Net-(U7-PA2)") (class "Default")
      (node (ref "JP2") (pin "3") (pinfunction "3_3") (pintype "passive"))
      (node (ref "U7") (pin "10") (pinfunction "PA2_10") (pintype "bidirectional"))
    )
    (net (code "81") (name "Net-(U7-PA3)") (class "Default")
      (node (ref "JP2") (pin "2") (pinfunction "2_2") (pintype "passive"))
      (node (ref "U7") (pin "11") (pinfunction "PA3_11") (pintype "bidirectional"))
    )
    (net (code "82") (name "Net-(U7-PA11)") (class "Default")
      (node (ref "U7") (pin "33") (pinfunction "PA11_33") (pintype "bidirectional"))
      (node (ref "U9") (pin "4") (pinfunction "RXD_4") (pintype "output"))
    )
    (net (code "83") (name "Net-(U7-PA12)") (class "Default")
      (node (ref "U7") (pin "34") (pinfunction "PA12_34") (pintype "bidirectional"))
      (node (ref "U9") (pin "1") (pinfunction "TXD_1") (pintype "input"))
    )
    (net (code "84") (name "Net-(U7-PA13)") (class "Default")
      (node (ref "JD3") (pin "3") (pinfunction "3_3") (pintype "passive"))
      (node (ref "U7") (pin "36") (pinfunction "PA13_36") (pintype "bidirectional"))
    )
    (net (code "85") (name "Net-(U7-PA14)") (class "Default")
      (node (ref "JD3") (pin "5") (pinfunction "5_5") (pintype "passive"))
      (node (ref "U7") (pin "37") (pinfunction "PA14_37") (pintype "bidirectional"))
    )
    (net (code "86") (name "Net-(U7-PF0-OSC_IN)") (class "Default")
      (node (ref "D5") (pin "CATHODE") (pinfunction "CATHODE_CATHODE") (pintype "power_in"))
      (node (ref "U7") (pin "5") (pinfunction "PF0-OSC_IN_5") (pintype "bidirectional"))
    )
    (net (code "87") (name "Net-(U7-PF1-OSC_OUT)") (class "Default")
      (node (ref "D4") (pin "CATHODE") (pinfunction "CATHODE_CATHODE") (pintype "power_in"))
      (node (ref "U7") (pin "6") (pinfunction "PF1-OSC_OUT_6") (pintype "bidirectional"))
    )
    (net (code "88") (name "Net-(U7-PG10-NRST)") (class "Default")
      (node (ref "C18") (pin "P$1") (pinfunction "P$1_P$1") (pintype "passive"))
      (node (ref "JD3") (pin "2") (pinfunction "2_2") (pintype "passive"))
      (node (ref "U7") (pin "7") (pinfunction "PG10-NRST_7") (pintype "bidirectional"))
    )
    (net (code "89") (name "Net-(U9-CANH)") (class "Default")
      (node (ref "JC5") (pin "1") (pinfunction "1_1") (pintype "passive"))
      (node (ref "R13") (pin "P$1") (pinfunction "P$1_P$1") (pintype "passive"))
      (node (ref "U9") (pin "7") (pinfunction "CANH_7") (pintype "bidirectional"))
    )
    (net (code "90") (name "Net-(U9-CANL)") (class "Default")
      (node (ref "JC5") (pin "2") (pinfunction "2_2") (pintype "passive"))
      (node (ref "R13") (pin "P$2") (pinfunction "P$2_P$2") (pintype "passive"))
      (node (ref "U9") (pin "6") (pinfunction "CANL_6") (pintype "bidirectional"))
    )
    (net (code "91") (name "Net-(U10-WP)") (class "Default")
      (node (ref "JP8") (pin "1") (pinfunction "1_1") (pintype "passive"))
      (node (ref "R14") (pin "P$2") (pinfunction "P$2_P$2") (pintype "passive"))
      (node (ref "U10") (pin "7") (pinfunction "WP_7") (pintype "bidirectional"))
    )
    (net (code "92") (name "Net-(U11-PA11)") (class "Default")
      (node (ref "U11") (pin "33") (pinfunction "PA11_33") (pintype "bidirectional"))
      (node (ref "U13") (pin "4") (pinfunction "RXD_4") (pintype "output"))
    )
    (net (code "93") (name "Net-(U11-PA12)") (class "Default")
      (node (ref "U11") (pin "34") (pinfunction "PA12_34") (pintype "bidirectional"))
      (node (ref "U13") (pin "1") (pinfunction "TXD_1") (pintype "input"))
    )
    (net (code "94") (name "Net-(U11-PA13)") (class "Default")
      (node (ref "JD2") (pin "3") (pinfunction "3_3") (pintype "passive"))
      (node (ref "U11") (pin "36") (pinfunction "PA13_36") (pintype "bidirectional"))
    )
    (net (code "95") (name "Net-(U11-PA14)") (class "Default")
      (node (ref "JD2") (pin "5") (pinfunction "5_5") (pintype "passive"))
      (node (ref "U11") (pin "37") (pinfunction "PA14_37") (pintype "bidirectional"))
    )
    (net (code "96") (name "Net-(U11-PB3)") (class "Default")
      (node (ref "U11") (pin "41") (pinfunction "PB3_41") (pintype "bidirectional"))
      (node (ref "U12") (pin "4") (pinfunction "RXD_4") (pintype "output"))
    )
    (net (code "97") (name "Net-(U11-PB4)") (class "Default")
      (node (ref "U11") (pin "42") (pinfunction "PB4_42") (pintype "bidirectional"))
      (node (ref "U12") (pin "1") (pinfunction "TXD_1") (pintype "input"))
    )
    (net (code "98") (name "Net-(U11-PB12)") (class "Default")
      (node (ref "JP3") (pin "2") (pinfunction "2_2") (pintype "passive"))
      (node (ref "U11") (pin "25") (pinfunction "PB12_25") (pintype "bidirectional"))
    )
    (net (code "99") (name "Net-(U11-PB13)") (class "Default")
      (node (ref "JP3") (pin "1") (pinfunction "1_1") (pintype "passive"))
      (node (ref "U11") (pin "26") (pinfunction "PB13_26") (pintype "bidirectional"))
    )
    (net (code "100") (name "Net-(U11-PF0-OSC_IN)") (class "Default")
      (node (ref "D7") (pin "CATHODE") (pinfunction "CATHODE_CATHODE") (pintype "power_in"))
      (node (ref "U11") (pin "5") (pinfunction "PF0-OSC_IN_5") (pintype "bidirectional"))
    )
    (net (code "101") (name "Net-(U11-PF1-OSC_OUT)") (class "Default")
      (node (ref "D6") (pin "CATHODE") (pinfunction "CATHODE_CATHODE") (pintype "power_in"))
      (node (ref "U11") (pin "6") (pinfunction "PF1-OSC_OUT_6") (pintype "bidirectional"))
    )
    (net (code "102") (name "Net-(U11-PG10-NRST)") (class "Default")
      (node (ref "C32") (pin "P$1") (pinfunction "P$1_P$1") (pintype "passive"))
      (node (ref "JD2") (pin "2") (pinfunction "2_2") (pintype "passive"))
      (node (ref "U11") (pin "7") (pinfunction "PG10-NRST_7") (pintype "bidirectional"))
    )
    (net (code "103") (name "Net-(U12-CANH)") (class "Default")
      (node (ref "JC3") (pin "1") (pinfunction "1_1") (pintype "passive"))
      (node (ref "R19") (pin "P$1") (pinfunction "P$1_P$1") (pintype "passive"))
      (node (ref "U12") (pin "7") (pinfunction "CANH_7") (pintype "bidirectional"))
    )
    (net (code "104") (name "Net-(U12-CANL)") (class "Default")
      (node (ref "JC3") (pin "2") (pinfunction "2_2") (pintype "passive"))
      (node (ref "R19") (pin "P$2") (pinfunction "P$2_P$2") (pintype "passive"))
      (node (ref "U12") (pin "6") (pinfunction "CANL_6") (pintype "bidirectional"))
    )
    (net (code "105") (name "Net-(U13-CANH)") (class "Default")
      (node (ref "JC4") (pin "1") (pinfunction "1_1") (pintype "passive"))
      (node (ref "R20") (pin "P$1") (pinfunction "P$1_P$1") (pintype "passive"))
      (node (ref "U13") (pin "7") (pinfunction "CANH_7") (pintype "bidirectional"))
    )
    (net (code "106") (name "Net-(U13-CANL)") (class "Default")
      (node (ref "JC4") (pin "2") (pinfunction "2_2") (pintype "passive"))
      (node (ref "R20") (pin "P$2") (pinfunction "P$2_P$2") (pintype "passive"))
      (node (ref "U13") (pin "6") (pinfunction "CANL_6") (pintype "bidirectional"))
    )
    (net (code "107") (name "unconnected-(J4-Pad7)") (class "Default")
      (node (ref "J4") (pin "7") (pinfunction "7_7") (pintype "passive"))
    )
    (net (code "108") (name "unconnected-(J4-Pad13)") (class "Default")
      (node (ref "J4") (pin "13") (pinfunction "13_13") (pintype "passive"))
    )
    (net (code "109") (name "unconnected-(J4-Pad22)") (class "Default")
      (node (ref "J4") (pin "22") (pinfunction "22_22") (pintype "passive"))
    )
    (net (code "110") (name "unconnected-(J4-Pad31)") (class "Default")
      (node (ref "J4") (pin "31") (pinfunction "31_31") (pintype "passive"))
    )
    (net (code "111") (name "unconnected-(JD1-Pad1)") (class "Default")
      (node (ref "JD1") (pin "1") (pinfunction "1_1") (pintype "passive"))
    )
    (net (code "112") (name "unconnected-(JD2-Pad1)") (class "Default")
      (node (ref "JD2") (pin "1") (pinfunction "1_1") (pintype "passive"))
    )
    (net (code "113") (name "unconnected-(JD3-Pad1)") (class "Default")
      (node (ref "JD3") (pin "1") (pinfunction "1_1") (pintype "passive"))
    )
    (net (code "114") (name "unconnected-(U1-CF-Pad8)") (class "Default")
      (node (ref "U1") (pin "8") (pinfunction "CF_8") (pintype "passive"))
    )
    (net (code "115") (name "unconnected-(U1-MODE-Pad11)") (class "Default")
      (node (ref "U1") (pin "11") (pinfunction "MODE_11") (pintype "passive"))
    )
    (net (code "116") (name "unconnected-(U1-RT-Pad10)") (class "Default")
      (node (ref "U1") (pin "10") (pinfunction "RT_10") (pintype "passive"))
    )
    (net (code "117") (name "unconnected-(U1-SYNC-Pad6)") (class "Default")
      (node (ref "U1") (pin "6") (pinfunction "SYNC_6") (pintype "passive"))
    )
    (net (code "118") (name "unconnected-(U1-~{RESET}-Pad5)") (class "Default")
      (node (ref "U1") (pin "5") (pinfunction "~{RESET}_5") (pintype "passive"))
    )
    (net (code "119") (name "unconnected-(U4-PA0-Pad8)") (class "Default")
      (node (ref "U4") (pin "8") (pinfunction "PA0_8") (pintype "bidirectional"))
    )
    (net (code "120") (name "unconnected-(U4-PA1-Pad9)") (class "Default")
      (node (ref "U4") (pin "9") (pinfunction "PA1_9") (pintype "bidirectional"))
    )
    (net (code "121") (name "unconnected-(U4-PA2-Pad10)") (class "Default")
      (node (ref "U4") (pin "10") (pinfunction "PA2_10") (pintype "bidirectional"))
    )
    (net (code "122") (name "unconnected-(U4-PA3-Pad11)") (class "Default")
      (node (ref "U4") (pin "11") (pinfunction "PA3_11") (pintype "bidirectional"))
    )
    (net (code "123") (name "unconnected-(U4-PA8-Pad30)") (class "Default")
      (node (ref "U4") (pin "30") (pinfunction "PA8_30") (pintype "bidirectional"))
    )
    (net (code "124") (name "unconnected-(U4-PA9-Pad31)") (class "Default")
      (node (ref "U4") (pin "31") (pinfunction "PA9_31") (pintype "bidirectional"))
    )
    (net (code "125") (name "unconnected-(U4-PA10-Pad32)") (class "Default")
      (node (ref "U4") (pin "32") (pinfunction "PA10_32") (pintype "bidirectional"))
    )
    (net (code "126") (name "unconnected-(U4-PA15-Pad38)") (class "Default")
      (node (ref "U4") (pin "38") (pinfunction "PA15_38") (pintype "bidirectional"))
    )
    (net (code "127") (name "unconnected-(U4-PB1-Pad18)") (class "Default")
      (node (ref "U4") (pin "18") (pinfunction "PB1_18") (pintype "bidirectional"))
    )
    (net (code "128") (name "unconnected-(U4-PB2-Pad19)") (class "Default")
      (node (ref "U4") (pin "19") (pinfunction "PB2_19") (pintype "bidirectional"))
    )
    (net (code "129") (name "unconnected-(U4-PB5-Pad43)") (class "Default")
      (node (ref "U4") (pin "43") (pinfunction "PB5_43") (pintype "bidirectional"))
    )
    (net (code "130") (name "unconnected-(U4-PB6-Pad44)") (class "Default")
      (node (ref "U4") (pin "44") (pinfunction "PB6_44") (pintype "bidirectional"))
    )
    (net (code "131") (name "unconnected-(U4-PB7-Pad45)") (class "Default")
      (node (ref "U4") (pin "45") (pinfunction "PB7_45") (pintype "bidirectional"))
    )
    (net (code "132") (name "unconnected-(U4-PB8-BOOT0-Pad46)") (class "Default")
      (node (ref "U4") (pin "46") (pinfunction "PB8-BOOT0_46") (pintype "bidirectional"))
    )
    (net (code "133") (name "unconnected-(U4-PB9-Pad47)") (class "Default")
      (node (ref "U4") (pin "47") (pinfunction "PB9_47") (pintype "bidirectional"))
    )
    (net (code "134") (name "unconnected-(U4-PB10-Pad22)") (class "Default")
      (node (ref "U4") (pin "22") (pinfunction "PB10_22") (pintype "bidirectional"))
    )
    (net (code "135") (name "unconnected-(U4-PB11-Pad24)") (class "Default")
      (node (ref "U4") (pin "24") (pinfunction "PB11_24") (pintype "bidirectional"))
    )
    (net (code "136") (name "unconnected-(U4-PB14-Pad27)") (class "Default")
      (node (ref "U4") (pin "27") (pinfunction "PB14_27") (pintype "bidirectional"))
    )
    (net (code "137") (name "unconnected-(U4-PB15-Pad28)") (class "Default")
      (node (ref "U4") (pin "28") (pinfunction "PB15_28") (pintype "bidirectional"))
    )
    (net (code "138") (name "unconnected-(U4-PC4-Pad16)") (class "Default")
      (node (ref "U4") (pin "16") (pinfunction "PC4_16") (pintype "bidirectional"))
    )
    (net (code "139") (name "unconnected-(U4-PC6-Pad29)") (class "Default")
      (node (ref "U4") (pin "29") (pinfunction "PC6_29") (pintype "bidirectional"))
    )
    (net (code "140") (name "unconnected-(U4-PC10-Pad39)") (class "Default")
      (node (ref "U4") (pin "39") (pinfunction "PC10_39") (pintype "bidirectional"))
    )
    (net (code "141") (name "unconnected-(U4-PC11-Pad40)") (class "Default")
      (node (ref "U4") (pin "40") (pinfunction "PC11_40") (pintype "bidirectional"))
    )
    (net (code "142") (name "unconnected-(U4-PC13-Pad2)") (class "Default")
      (node (ref "U4") (pin "2") (pinfunction "PC13_2") (pintype "bidirectional"))
    )
    (net (code "143") (name "unconnected-(U7-PB8-BOOT0-Pad46)") (class "Default")
      (node (ref "U7") (pin "46") (pinfunction "PB8-BOOT0_46") (pintype "bidirectional"))
    )
    (net (code "144") (name "unconnected-(U7-PB9-Pad47)") (class "Default")
      (node (ref "U7") (pin "47") (pinfunction "PB9_47") (pintype "bidirectional"))
    )
    (net (code "145") (name "unconnected-(U7-PC10-Pad39)") (class "Default")
      (node (ref "U7") (pin "39") (pinfunction "PC10_39") (pintype "bidirectional"))
    )
    (net (code "146") (name "unconnected-(U7-PC11-Pad40)") (class "Default")
      (node (ref "U7") (pin "40") (pinfunction "PC11_40") (pintype "bidirectional"))
    )
    (net (code "147") (name "unconnected-(U7-PC13-Pad2)") (class "Default")
      (node (ref "U7") (pin "2") (pinfunction "PC13_2") (pintype "bidirectional"))
    )
    (net (code "148") (name "unconnected-(U8-INT2-Pad1)") (class "Default")
      (node (ref "U8") (pin "1") (pinfunction "INT2_1") (pintype "bidirectional"))
    )
    (net (code "149") (name "unconnected-(U8-INT4-Pad13)") (class "Default")
      (node (ref "U8") (pin "13") (pinfunction "INT4_13") (pintype "bidirectional"))
    )
    (net (code "150") (name "unconnected-(U8-NC-Pad2)") (class "Default")
      (node (ref "U8") (pin "2") (pinfunction "NC_2") (pintype "bidirectional"))
    )
    (net (code "151") (name "unconnected-(U9-SPLIT-Pad5)") (class "Default")
      (node (ref "U9") (pin "5") (pinfunction "SPLIT_5") (pintype "input"))
    )
    (net (code "152") (name "unconnected-(U11-PA0-Pad8)") (class "Default")
      (node (ref "U11") (pin "8") (pinfunction "PA0_8") (pintype "bidirectional"))
    )
    (net (code "153") (name "unconnected-(U11-PA1-Pad9)") (class "Default")
      (node (ref "U11") (pin "9") (pinfunction "PA1_9") (pintype "bidirectional"))
    )
    (net (code "154") (name "unconnected-(U11-PA2-Pad10)") (class "Default")
      (node (ref "U11") (pin "10") (pinfunction "PA2_10") (pintype "bidirectional"))
    )
    (net (code "155") (name "unconnected-(U11-PA3-Pad11)") (class "Default")
      (node (ref "U11") (pin "11") (pinfunction "PA3_11") (pintype "bidirectional"))
    )
    (net (code "156") (name "unconnected-(U11-PA8-Pad30)") (class "Default")
      (node (ref "U11") (pin "30") (pinfunction "PA8_30") (pintype "bidirectional"))
    )
    (net (code "157") (name "unconnected-(U11-PA9-Pad31)") (class "Default")
      (node (ref "U11") (pin "31") (pinfunction "PA9_31") (pintype "bidirectional"))
    )
    (net (code "158") (name "unconnected-(U11-PA10-Pad32)") (class "Default")
      (node (ref "U11") (pin "32") (pinfunction "PA10_32") (pintype "bidirectional"))
    )
    (net (code "159") (name "unconnected-(U11-PA15-Pad38)") (class "Default")
      (node (ref "U11") (pin "38") (pinfunction "PA15_38") (pintype "bidirectional"))
    )
    (net (code "160") (name "unconnected-(U11-PB1-Pad18)") (class "Default")
      (node (ref "U11") (pin "18") (pinfunction "PB1_18") (pintype "bidirectional"))
    )
    (net (code "161") (name "unconnected-(U11-PB2-Pad19)") (class "Default")
      (node (ref "U11") (pin "19") (pinfunction "PB2_19") (pintype "bidirectional"))
    )
    (net (code "162") (name "unconnected-(U11-PB5-Pad43)") (class "Default")
      (node (ref "U11") (pin "43") (pinfunction "PB5_43") (pintype "bidirectional"))
    )
    (net (code "163") (name "unconnected-(U11-PB6-Pad44)") (class "Default")
      (node (ref "U11") (pin "44") (pinfunction "PB6_44") (pintype "bidirectional"))
    )
    (net (code "164") (name "unconnected-(U11-PB7-Pad45)") (class "Default")
      (node (ref "U11") (pin "45") (pinfunction "PB7_45") (pintype "bidirectional"))
    )
    (net (code "165") (name "unconnected-(U11-PB8-BOOT0-Pad46)") (class "Default")
      (node (ref "U11") (pin "46") (pinfunction "PB8-BOOT0_46") (pintype "bidirectional"))
    )
    (net (code "166") (name "unconnected-(U11-PB9-Pad47)") (class "Default")
      (node (ref "U11") (pin "47") (pinfunction "PB9_47") (pintype "bidirectional"))
    )
    (net (code "167") (name "unconnected-(U11-PB10-Pad22)") (class "Default")
      (node (ref "U11") (pin "22") (pinfunction "PB10_22") (pintype "bidirectional"))
    )
    (net (code "168") (name "unconnected-(U11-PB11-Pad24)") (class "Default")
      (node (ref "U11") (pin "24") (pinfunction "PB11_24") (pintype "bidirectional"))
    )
    (net (code "169") (name "unconnected-(U11-PB14-Pad27)") (class "Default")
      (node (ref "U11") (pin "27") (pinfunction "PB14_27") (pintype "bidirectional"))
    )
    (net (code "170") (name "unconnected-(U11-PB15-Pad28)") (class "Default")
      (node (ref "U11") (pin "28") (pinfunction "PB15_28") (pintype "bidirectional"))
    )
    (net (code "171") (name "unconnected-(U11-PC4-Pad16)") (class "Default")
      (node (ref "U11") (pin "16") (pinfunction "PC4_16") (pintype "bidirectional"))
    )
    (net (code "172") (name "unconnected-(U11-PC6-Pad29)") (class "Default")
      (node (ref "U11") (pin "29") (pinfunction "PC6_29") (pintype "bidirectional"))
    )
    (net (code "173") (name "unconnected-(U11-PC10-Pad39)") (class "Default")
      (node (ref "U11") (pin "39") (pinfunction "PC10_39") (pintype "bidirectional"))
    )
    (net (code "174") (name "unconnected-(U11-PC11-Pad40)") (class "Default")
      (node (ref "U11") (pin "40") (pinfunction "PC11_40") (pintype "bidirectional"))
    )
    (net (code "175") (name "unconnected-(U11-PC13-Pad2)") (class "Default")
      (node (ref "U11") (pin "2") (pinfunction "PC13_2") (pintype "bidirectional"))
    )
    (net (code "176") (name "unconnected-(U14-RESV_2-Pad2)") (class "Default")
      (node (ref "U14") (pin "2") (pinfunction "RESV_2_2") (pintype "passive"))
    )
    (net (code "177") (name "unconnected-(U14-RESV_3-Pad3)") (class "Default")
      (node (ref "U14") (pin "3") (pinfunction "RESV_3_3") (pintype "passive"))
    )
    (net (code "178") (name "unconnected-(U14-RESV_7-Pad7)") (class "Default")
      (node (ref "U14") (pin "7") (pinfunction "RESV_7_7") (pintype "passive"))
    )
    (net (code "179") (name "unconnected-(U14-RESV_10-Pad10)") (class "Default")
      (node (ref "U14") (pin "10") (pinfunction "RESV_10_10") (pintype "passive"))
    )
    (net (code "180") (name "unconnected-(U14-RESV_11-Pad11)") (class "Default")
      (node (ref "U14") (pin "11") (pinfunction "RESV_11_11") (pintype "passive"))
    )
  )
)
